# 2_waffling80-NMB_matrix.net
KiCad netlist of a schematic drawn in Altium Designer
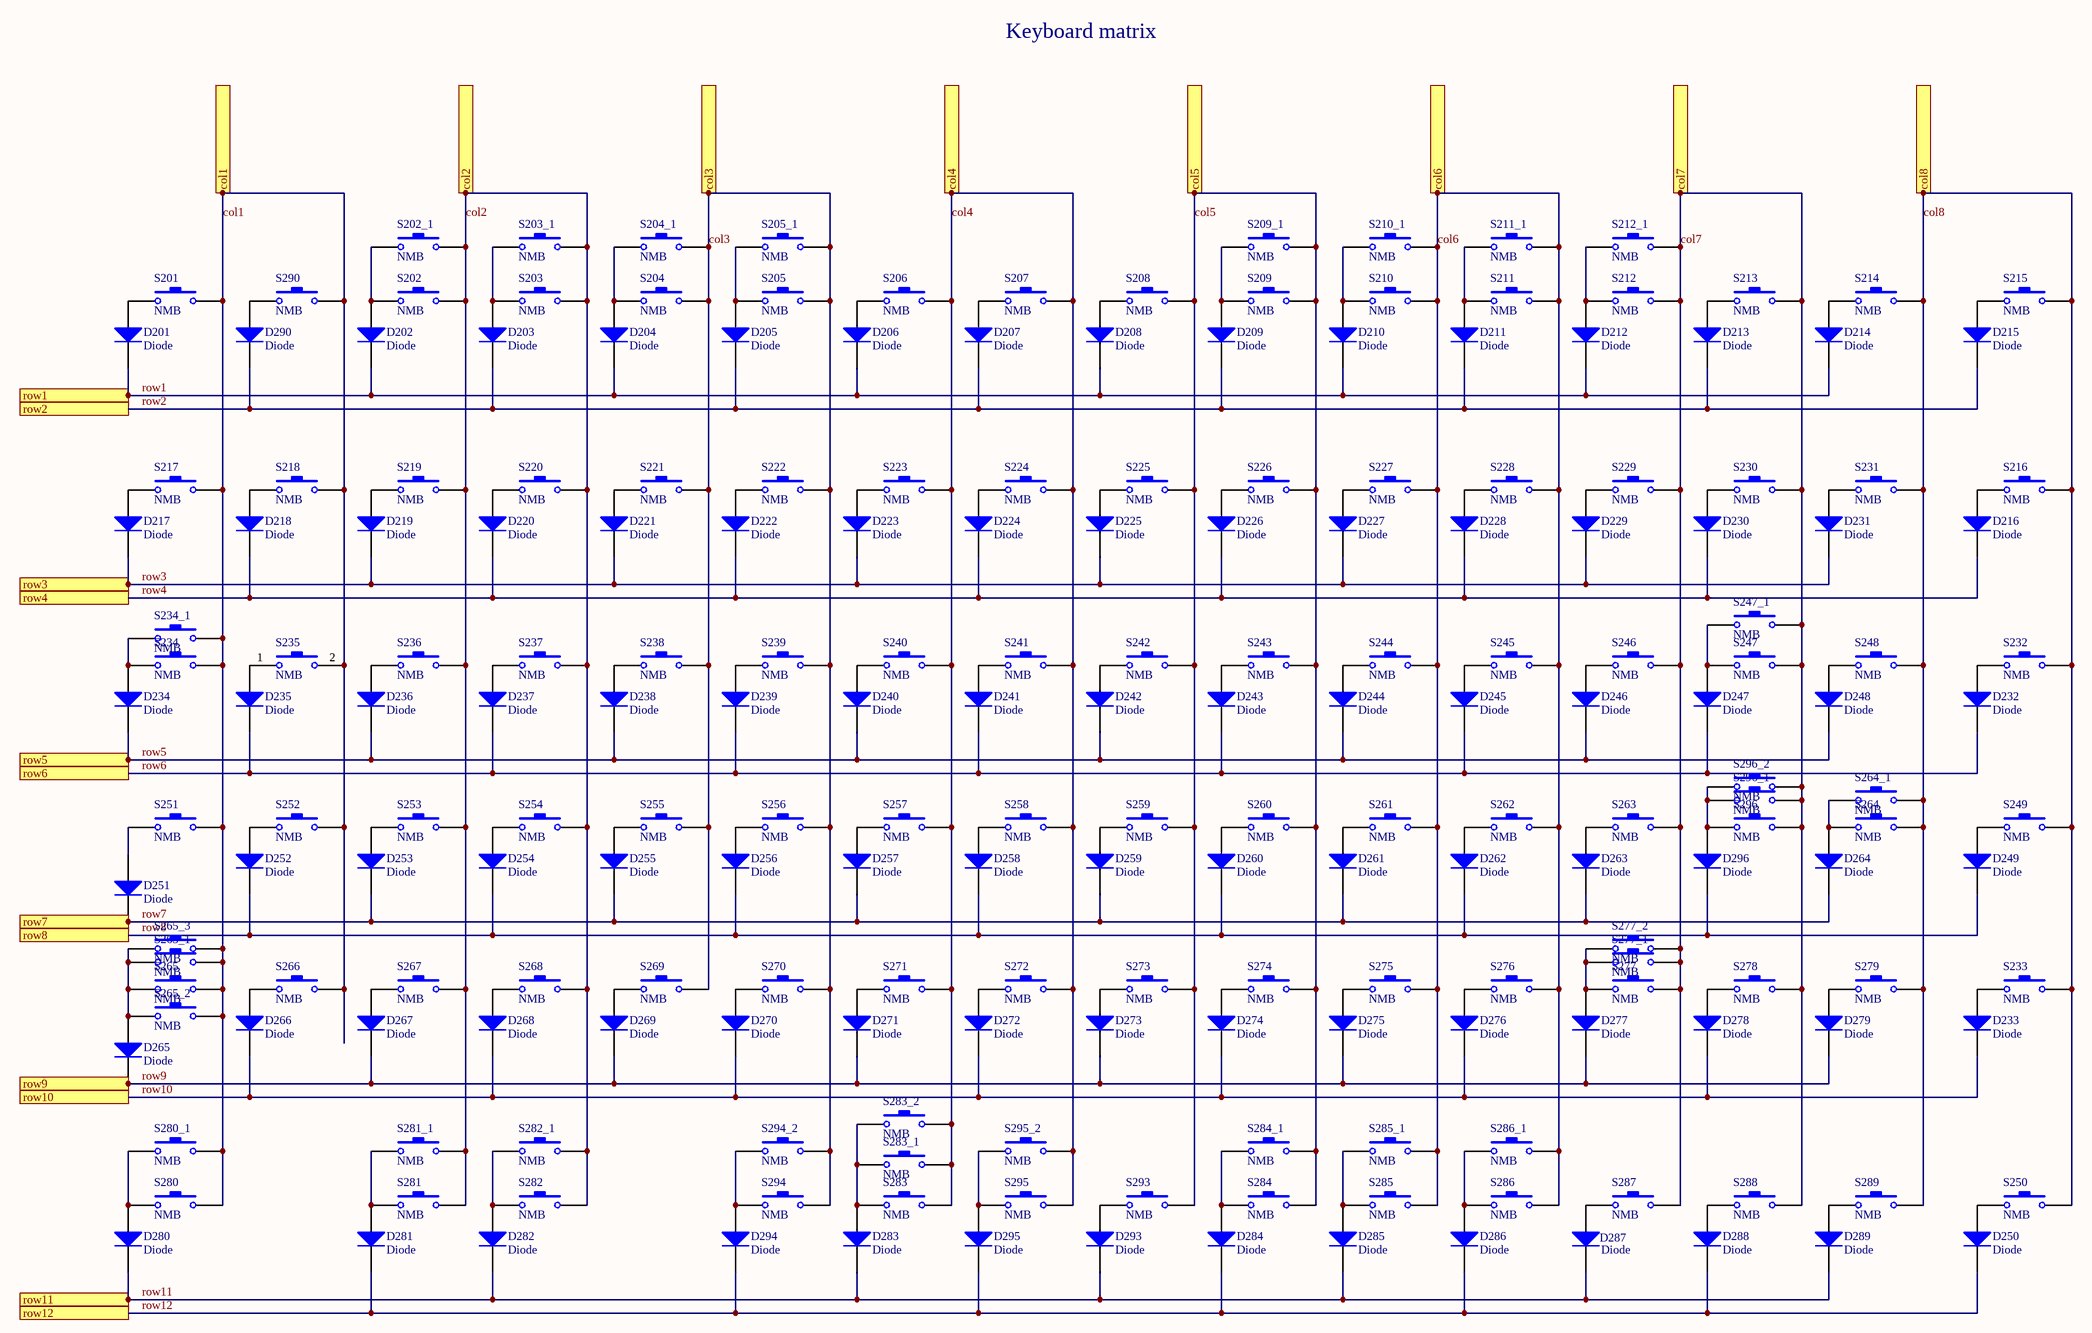
[diagram p0: 2_waffling80-NMB_matrix.SchDoc]

(export (version "E")
  (design (tool "Eeschema 10.0.6"))
  (components
    (comp (ref "D201")
      (value "Diode")
      (footprint "SOD-123")
      (description "Default Diode")
      (fields (field (name "LCSC PART #") "C81598") (field (name "MRF.PART") "1N4148W"))
      (libsource (lib "Miscellaneous Devices") (part "Diode"))
    )
    (comp (ref "D202")
      (value "Diode")
      (footprint "SOD-123")
      (description "Default Diode")
      (fields (field (name "LCSC PART #") "C81598") (field (name "MRF.PART") "1N4148W"))
      (libsource (lib "Miscellaneous Devices") (part "Diode"))
    )
    (comp (ref "D203")
      (value "Diode")
      (footprint "SOD-123")
      (description "Default Diode")
      (fields (field (name "LCSC PART #") "C81598") (field (name "MRF.PART") "1N4148W"))
      (libsource (lib "Miscellaneous Devices") (part "Diode"))
    )
    (comp (ref "D204")
      (value "Diode")
      (footprint "SOD-123")
      (description "Default Diode")
      (fields (field (name "LCSC PART #") "C81598") (field (name "MRF.PART") "1N4148W"))
      (libsource (lib "Miscellaneous Devices") (part "Diode"))
    )
    (comp (ref "D205")
      (value "Diode")
      (footprint "SOD-123")
      (description "Default Diode")
      (fields (field (name "LCSC PART #") "C81598") (field (name "MRF.PART") "1N4148W"))
      (libsource (lib "Miscellaneous Devices") (part "Diode"))
    )
    (comp (ref "D206")
      (value "Diode")
      (footprint "SOD-123")
      (description "Default Diode")
      (fields (field (name "LCSC PART #") "C81598") (field (name "MRF.PART") "1N4148W"))
      (libsource (lib "Miscellaneous Devices") (part "Diode"))
    )
    (comp (ref "D207")
      (value "Diode")
      (footprint "SOD-123")
      (description "Default Diode")
      (fields (field (name "LCSC PART #") "C81598") (field (name "MRF.PART") "1N4148W"))
      (libsource (lib "Miscellaneous Devices") (part "Diode"))
    )
    (comp (ref "D208")
      (value "Diode")
      (footprint "SOD-123")
      (description "Default Diode")
      (fields (field (name "LCSC PART #") "C81598") (field (name "MRF.PART") "1N4148W"))
      (libsource (lib "Miscellaneous Devices") (part "Diode"))
    )
    (comp (ref "D209")
      (value "Diode")
      (footprint "SOD-123")
      (description "Default Diode")
      (fields (field (name "LCSC PART #") "C81598") (field (name "MRF.PART") "1N4148W"))
      (libsource (lib "Miscellaneous Devices") (part "Diode"))
    )
    (comp (ref "D210")
      (value "Diode")
      (footprint "SOD-123")
      (description "Default Diode")
      (fields (field (name "LCSC PART #") "C81598") (field (name "MRF.PART") "1N4148W"))
      (libsource (lib "Miscellaneous Devices") (part "Diode"))
    )
    (comp (ref "D211")
      (value "Diode")
      (footprint "SOD-123")
      (description "Default Diode")
      (fields (field (name "LCSC PART #") "C81598") (field (name "MRF.PART") "1N4148W"))
      (libsource (lib "Miscellaneous Devices") (part "Diode"))
    )
    (comp (ref "D212")
      (value "Diode")
      (footprint "SOD-123")
      (description "Default Diode")
      (fields (field (name "LCSC PART #") "C81598") (field (name "MRF.PART") "1N4148W"))
      (libsource (lib "Miscellaneous Devices") (part "Diode"))
    )
    (comp (ref "D213")
      (value "Diode")
      (footprint "SOD-123")
      (description "Default Diode")
      (fields (field (name "LCSC PART #") "C81598") (field (name "MRF.PART") "1N4148W"))
      (libsource (lib "Miscellaneous Devices") (part "Diode"))
    )
    (comp (ref "D214")
      (value "Diode")
      (footprint "SOD-123")
      (description "Default Diode")
      (fields (field (name "LCSC PART #") "C81598") (field (name "MRF.PART") "1N4148W"))
      (libsource (lib "Miscellaneous Devices") (part "Diode"))
    )
    (comp (ref "D215")
      (value "Diode")
      (footprint "SOD-123")
      (description "Default Diode")
      (fields (field (name "LCSC PART #") "C81598") (field (name "MRF.PART") "1N4148W"))
      (libsource (lib "Miscellaneous Devices") (part "Diode"))
    )
    (comp (ref "D216")
      (value "Diode")
      (footprint "SOD-123")
      (description "Default Diode")
      (fields (field (name "LCSC PART #") "C81598") (field (name "MRF.PART") "1N4148W"))
      (libsource (lib "Miscellaneous Devices") (part "Diode"))
    )
    (comp (ref "D217")
      (value "Diode")
      (footprint "SOD-123")
      (description "Default Diode")
      (fields (field (name "LCSC PART #") "C81598") (field (name "MRF.PART") "1N4148W"))
      (libsource (lib "Miscellaneous Devices") (part "Diode"))
    )
    (comp (ref "D218")
      (value "Diode")
      (footprint "SOD-123")
      (description "Default Diode")
      (fields (field (name "LCSC PART #") "C81598") (field (name "MRF.PART") "1N4148W"))
      (libsource (lib "Miscellaneous Devices") (part "Diode"))
    )
    (comp (ref "D219")
      (value "Diode")
      (footprint "SOD-123")
      (description "Default Diode")
      (fields (field (name "LCSC PART #") "C81598") (field (name "MRF.PART") "1N4148W"))
      (libsource (lib "Miscellaneous Devices") (part "Diode"))
    )
    (comp (ref "D220")
      (value "Diode")
      (footprint "SOD-123")
      (description "Default Diode")
      (fields (field (name "LCSC PART #") "C81598") (field (name "MRF.PART") "1N4148W"))
      (libsource (lib "Miscellaneous Devices") (part "Diode"))
    )
    (comp (ref "D221")
      (value "Diode")
      (footprint "SOD-123")
      (description "Default Diode")
      (fields (field (name "LCSC PART #") "C81598") (field (name "MRF.PART") "1N4148W"))
      (libsource (lib "Miscellaneous Devices") (part "Diode"))
    )
    (comp (ref "D222")
      (value "Diode")
      (footprint "SOD-123")
      (description "Default Diode")
      (fields (field (name "LCSC PART #") "C81598") (field (name "MRF.PART") "1N4148W"))
      (libsource (lib "Miscellaneous Devices") (part "Diode"))
    )
    (comp (ref "D223")
      (value "Diode")
      (footprint "SOD-123")
      (description "Default Diode")
      (fields (field (name "LCSC PART #") "C81598") (field (name "MRF.PART") "1N4148W"))
      (libsource (lib "Miscellaneous Devices") (part "Diode"))
    )
    (comp (ref "D224")
      (value "Diode")
      (footprint "SOD-123")
      (description "Default Diode")
      (fields (field (name "LCSC PART #") "C81598") (field (name "MRF.PART") "1N4148W"))
      (libsource (lib "Miscellaneous Devices") (part "Diode"))
    )
    (comp (ref "D225")
      (value "Diode")
      (footprint "SOD-123")
      (description "Default Diode")
      (fields (field (name "LCSC PART #") "C81598") (field (name "MRF.PART") "1N4148W"))
      (libsource (lib "Miscellaneous Devices") (part "Diode"))
    )
    (comp (ref "D226")
      (value "Diode")
      (footprint "SOD-123")
      (description "Default Diode")
      (fields (field (name "LCSC PART #") "C81598") (field (name "MRF.PART") "1N4148W"))
      (libsource (lib "Miscellaneous Devices") (part "Diode"))
    )
    (comp (ref "D227")
      (value "Diode")
      (footprint "SOD-123")
      (description "Default Diode")
      (fields (field (name "LCSC PART #") "C81598") (field (name "MRF.PART") "1N4148W"))
      (libsource (lib "Miscellaneous Devices") (part "Diode"))
    )
    (comp (ref "D228")
      (value "Diode")
      (footprint "SOD-123")
      (description "Default Diode")
      (fields (field (name "LCSC PART #") "C81598") (field (name "MRF.PART") "1N4148W"))
      (libsource (lib "Miscellaneous Devices") (part "Diode"))
    )
    (comp (ref "D229")
      (value "Diode")
      (footprint "SOD-123")
      (description "Default Diode")
      (fields (field (name "LCSC PART #") "C81598") (field (name "MRF.PART") "1N4148W"))
      (libsource (lib "Miscellaneous Devices") (part "Diode"))
    )
    (comp (ref "D230")
      (value "Diode")
      (footprint "SOD-123")
      (description "Default Diode")
      (fields (field (name "LCSC PART #") "C81598") (field (name "MRF.PART") "1N4148W"))
      (libsource (lib "Miscellaneous Devices") (part "Diode"))
    )
    (comp (ref "D231")
      (value "Diode")
      (footprint "SOD-123")
      (description "Default Diode")
      (fields (field (name "LCSC PART #") "C81598") (field (name "MRF.PART") "1N4148W"))
      (libsource (lib "Miscellaneous Devices") (part "Diode"))
    )
    (comp (ref "D232")
      (value "Diode")
      (footprint "SOD-123")
      (description "Default Diode")
      (fields (field (name "LCSC PART #") "C81598") (field (name "MRF.PART") "1N4148W"))
      (libsource (lib "Miscellaneous Devices") (part "Diode"))
    )
    (comp (ref "D233")
      (value "Diode")
      (footprint "SOD-123")
      (description "Default Diode")
      (fields (field (name "LCSC PART #") "C81598") (field (name "MRF.PART") "1N4148W"))
      (libsource (lib "Miscellaneous Devices") (part "Diode"))
    )
    (comp (ref "D234")
      (value "Diode")
      (footprint "SOD-123")
      (description "Default Diode")
      (fields (field (name "LCSC PART #") "C81598") (field (name "MRF.PART") "1N4148W"))
      (libsource (lib "Miscellaneous Devices") (part "Diode"))
    )
    (comp (ref "D235")
      (value "Diode")
      (footprint "SOD-123")
      (description "Default Diode")
      (fields (field (name "LCSC PART #") "C81598") (field (name "MRF.PART") "1N4148W"))
      (libsource (lib "Miscellaneous Devices") (part "Diode"))
    )
    (comp (ref "D236")
      (value "Diode")
      (footprint "SOD-123")
      (description "Default Diode")
      (fields (field (name "LCSC PART #") "C81598") (field (name "MRF.PART") "1N4148W"))
      (libsource (lib "Miscellaneous Devices") (part "Diode"))
    )
    (comp (ref "D237")
      (value "Diode")
      (footprint "SOD-123")
      (description "Default Diode")
      (fields (field (name "LCSC PART #") "C81598") (field (name "MRF.PART") "1N4148W"))
      (libsource (lib "Miscellaneous Devices") (part "Diode"))
    )
    (comp (ref "D238")
      (value "Diode")
      (footprint "SOD-123")
      (description "Default Diode")
      (fields (field (name "LCSC PART #") "C81598") (field (name "MRF.PART") "1N4148W"))
      (libsource (lib "Miscellaneous Devices") (part "Diode"))
    )
    (comp (ref "D239")
      (value "Diode")
      (footprint "SOD-123")
      (description "Default Diode")
      (fields (field (name "LCSC PART #") "C81598") (field (name "MRF.PART") "1N4148W"))
      (libsource (lib "Miscellaneous Devices") (part "Diode"))
    )
    (comp (ref "D240")
      (value "Diode")
      (footprint "SOD-123")
      (description "Default Diode")
      (fields (field (name "LCSC PART #") "C81598") (field (name "MRF.PART") "1N4148W"))
      (libsource (lib "Miscellaneous Devices") (part "Diode"))
    )
    (comp (ref "D241")
      (value "Diode")
      (footprint "SOD-123")
      (description "Default Diode")
      (fields (field (name "LCSC PART #") "C81598") (field (name "MRF.PART") "1N4148W"))
      (libsource (lib "Miscellaneous Devices") (part "Diode"))
    )
    (comp (ref "D242")
      (value "Diode")
      (footprint "SOD-123")
      (description "Default Diode")
      (fields (field (name "LCSC PART #") "C81598") (field (name "MRF.PART") "1N4148W"))
      (libsource (lib "Miscellaneous Devices") (part "Diode"))
    )
    (comp (ref "D243")
      (value "Diode")
      (footprint "SOD-123")
      (description "Default Diode")
      (fields (field (name "LCSC PART #") "C81598") (field (name "MRF.PART") "1N4148W"))
      (libsource (lib "Miscellaneous Devices") (part "Diode"))
    )
    (comp (ref "D244")
      (value "Diode")
      (footprint "SOD-123")
      (description "Default Diode")
      (fields (field (name "LCSC PART #") "C81598") (field (name "MRF.PART") "1N4148W"))
      (libsource (lib "Miscellaneous Devices") (part "Diode"))
    )
    (comp (ref "D245")
      (value "Diode")
      (footprint "SOD-123")
      (description "Default Diode")
      (fields (field (name "LCSC PART #") "C81598") (field (name "MRF.PART") "1N4148W"))
      (libsource (lib "Miscellaneous Devices") (part "Diode"))
    )
    (comp (ref "D246")
      (value "Diode")
      (footprint "SOD-123")
      (description "Default Diode")
      (fields (field (name "LCSC PART #") "C81598") (field (name "MRF.PART") "1N4148W"))
      (libsource (lib "Miscellaneous Devices") (part "Diode"))
    )
    (comp (ref "D247")
      (value "Diode")
      (footprint "SOD-123")
      (description "Default Diode")
      (fields (field (name "LCSC PART #") "C81598") (field (name "MRF.PART") "1N4148W"))
      (libsource (lib "Miscellaneous Devices") (part "Diode"))
    )
    (comp (ref "D248")
      (value "Diode")
      (footprint "SOD-123")
      (description "Default Diode")
      (fields (field (name "LCSC PART #") "C81598") (field (name "MRF.PART") "1N4148W"))
      (libsource (lib "Miscellaneous Devices") (part "Diode"))
    )
    (comp (ref "D249")
      (value "Diode")
      (footprint "SOD-123")
      (description "Default Diode")
      (fields (field (name "LCSC PART #") "C81598") (field (name "MRF.PART") "1N4148W"))
      (libsource (lib "Miscellaneous Devices") (part "Diode"))
    )
    (comp (ref "D250")
      (value "Diode")
      (footprint "SOD-123")
      (description "Default Diode")
      (fields (field (name "LCSC PART #") "C81598") (field (name "MRF.PART") "1N4148W"))
      (libsource (lib "Miscellaneous Devices") (part "Diode"))
    )
    (comp (ref "D251")
      (value "Diode")
      (footprint "SOD-123")
      (description "Default Diode")
      (fields (field (name "LCSC PART #") "C81598") (field (name "MRF.PART") "1N4148W"))
      (libsource (lib "Miscellaneous Devices") (part "Diode"))
    )
    (comp (ref "D252")
      (value "Diode")
      (footprint "SOD-123")
      (description "Default Diode")
      (fields (field (name "LCSC PART #") "C81598") (field (name "MRF.PART") "1N4148W"))
      (libsource (lib "Miscellaneous Devices") (part "Diode"))
    )
    (comp (ref "D253")
      (value "Diode")
      (footprint "SOD-123")
      (description "Default Diode")
      (fields (field (name "LCSC PART #") "C81598") (field (name "MRF.PART") "1N4148W"))
      (libsource (lib "Miscellaneous Devices") (part "Diode"))
    )
    (comp (ref "D254")
      (value "Diode")
      (footprint "SOD-123")
      (description "Default Diode")
      (fields (field (name "LCSC PART #") "C81598") (field (name "MRF.PART") "1N4148W"))
      (libsource (lib "Miscellaneous Devices") (part "Diode"))
    )
    (comp (ref "D255")
      (value "Diode")
      (footprint "SOD-123")
      (description "Default Diode")
      (fields (field (name "LCSC PART #") "C81598") (field (name "MRF.PART") "1N4148W"))
      (libsource (lib "Miscellaneous Devices") (part "Diode"))
    )
    (comp (ref "D256")
      (value "Diode")
      (footprint "SOD-123")
      (description "Default Diode")
      (fields (field (name "LCSC PART #") "C81598") (field (name "MRF.PART") "1N4148W"))
      (libsource (lib "Miscellaneous Devices") (part "Diode"))
    )
    (comp (ref "D257")
      (value "Diode")
      (footprint "SOD-123")
      (description "Default Diode")
      (fields (field (name "LCSC PART #") "C81598") (field (name "MRF.PART") "1N4148W"))
      (libsource (lib "Miscellaneous Devices") (part "Diode"))
    )
    (comp (ref "D258")
      (value "Diode")
      (footprint "SOD-123")
      (description "Default Diode")
      (fields (field (name "LCSC PART #") "C81598") (field (name "MRF.PART") "1N4148W"))
      (libsource (lib "Miscellaneous Devices") (part "Diode"))
    )
    (comp (ref "D259")
      (value "Diode")
      (footprint "SOD-123")
      (description "Default Diode")
      (fields (field (name "LCSC PART #") "C81598") (field (name "MRF.PART") "1N4148W"))
      (libsource (lib "Miscellaneous Devices") (part "Diode"))
    )
    (comp (ref "D260")
      (value "Diode")
      (footprint "SOD-123")
      (description "Default Diode")
      (fields (field (name "LCSC PART #") "C81598") (field (name "MRF.PART") "1N4148W"))
      (libsource (lib "Miscellaneous Devices") (part "Diode"))
    )
    (comp (ref "D261")
      (value "Diode")
      (footprint "SOD-123")
      (description "Default Diode")
      (fields (field (name "LCSC PART #") "C81598") (field (name "MRF.PART") "1N4148W"))
      (libsource (lib "Miscellaneous Devices") (part "Diode"))
    )
    (comp (ref "D262")
      (value "Diode")
      (footprint "SOD-123")
      (description "Default Diode")
      (fields (field (name "LCSC PART #") "C81598") (field (name "MRF.PART") "1N4148W"))
      (libsource (lib "Miscellaneous Devices") (part "Diode"))
    )
    (comp (ref "D263")
      (value "Diode")
      (footprint "SOD-123")
      (description "Default Diode")
      (fields (field (name "LCSC PART #") "C81598") (field (name "MRF.PART") "1N4148W"))
      (libsource (lib "Miscellaneous Devices") (part "Diode"))
    )
    (comp (ref "D264")
      (value "Diode")
      (footprint "SOD-123")
      (description "Default Diode")
      (fields (field (name "LCSC PART #") "C81598") (field (name "MRF.PART") "1N4148W"))
      (libsource (lib "Miscellaneous Devices") (part "Diode"))
    )
    (comp (ref "D265")
      (value "Diode")
      (footprint "SOD-123")
      (description "Default Diode")
      (fields (field (name "LCSC PART #") "C81598") (field (name "MRF.PART") "1N4148W"))
      (libsource (lib "Miscellaneous Devices") (part "Diode"))
    )
    (comp (ref "D266")
      (value "Diode")
      (footprint "SOD-123")
      (description "Default Diode")
      (fields (field (name "LCSC PART #") "C81598") (field (name "MRF.PART") "1N4148W"))
      (libsource (lib "Miscellaneous Devices") (part "Diode"))
    )
    (comp (ref "D267")
      (value "Diode")
      (footprint "SOD-123")
      (description "Default Diode")
      (fields (field (name "LCSC PART #") "C81598") (field (name "MRF.PART") "1N4148W"))
      (libsource (lib "Miscellaneous Devices") (part "Diode"))
    )
    (comp (ref "D268")
      (value "Diode")
      (footprint "SOD-123")
      (description "Default Diode")
      (fields (field (name "LCSC PART #") "C81598") (field (name "MRF.PART") "1N4148W"))
      (libsource (lib "Miscellaneous Devices") (part "Diode"))
    )
    (comp (ref "D269")
      (value "Diode")
      (footprint "SOD-123")
      (description "Default Diode")
      (fields (field (name "LCSC PART #") "C81598") (field (name "MRF.PART") "1N4148W"))
      (libsource (lib "Miscellaneous Devices") (part "Diode"))
    )
    (comp (ref "D270")
      (value "Diode")
      (footprint "SOD-123")
      (description "Default Diode")
      (fields (field (name "LCSC PART #") "C81598") (field (name "MRF.PART") "1N4148W"))
      (libsource (lib "Miscellaneous Devices") (part "Diode"))
    )
    (comp (ref "D271")
      (value "Diode")
      (footprint "SOD-123")
      (description "Default Diode")
      (fields (field (name "LCSC PART #") "C81598") (field (name "MRF.PART") "1N4148W"))
      (libsource (lib "Miscellaneous Devices") (part "Diode"))
    )
    (comp (ref "D272")
      (value "Diode")
      (footprint "SOD-123")
      (description "Default Diode")
      (fields (field (name "LCSC PART #") "C81598") (field (name "MRF.PART") "1N4148W"))
      (libsource (lib "Miscellaneous Devices") (part "Diode"))
    )
    (comp (ref "D273")
      (value "Diode")
      (footprint "SOD-123")
      (description "Default Diode")
      (fields (field (name "LCSC PART #") "C81598") (field (name "MRF.PART") "1N4148W"))
      (libsource (lib "Miscellaneous Devices") (part "Diode"))
    )
    (comp (ref "D274")
      (value "Diode")
      (footprint "SOD-123")
      (description "Default Diode")
      (fields (field (name "LCSC PART #") "C81598") (field (name "MRF.PART") "1N4148W"))
      (libsource (lib "Miscellaneous Devices") (part "Diode"))
    )
    (comp (ref "D275")
      (value "Diode")
      (footprint "SOD-123")
      (description "Default Diode")
      (fields (field (name "LCSC PART #") "C81598") (field (name "MRF.PART") "1N4148W"))
      (libsource (lib "Miscellaneous Devices") (part "Diode"))
    )
    (comp (ref "D276")
      (value "Diode")
      (footprint "SOD-123")
      (description "Default Diode")
      (fields (field (name "LCSC PART #") "C81598") (field (name "MRF.PART") "1N4148W"))
      (libsource (lib "Miscellaneous Devices") (part "Diode"))
    )
    (comp (ref "D277")
      (value "Diode")
      (footprint "SOD-123")
      (description "Default Diode")
      (fields (field (name "LCSC PART #") "C81598") (field (name "MRF.PART") "1N4148W"))
      (libsource (lib "Miscellaneous Devices") (part "Diode"))
    )
    (comp (ref "D278")
      (value "Diode")
      (footprint "SOD-123")
      (description "Default Diode")
      (fields (field (name "LCSC PART #") "C81598") (field (name "MRF.PART") "1N4148W"))
      (libsource (lib "Miscellaneous Devices") (part "Diode"))
    )
    (comp (ref "D279")
      (value "Diode")
      (footprint "SOD-123")
      (description "Default Diode")
      (fields (field (name "LCSC PART #") "C81598") (field (name "MRF.PART") "1N4148W"))
      (libsource (lib "Miscellaneous Devices") (part "Diode"))
    )
    (comp (ref "D280")
      (value "Diode")
      (footprint "SOD-123")
      (description "Default Diode")
      (fields (field (name "LCSC PART #") "C81598") (field (name "MRF.PART") "1N4148W"))
      (libsource (lib "Miscellaneous Devices") (part "Diode"))
    )
    (comp (ref "D281")
      (value "Diode")
      (footprint "SOD-123")
      (description "Default Diode")
      (fields (field (name "LCSC PART #") "C81598") (field (name "MRF.PART") "1N4148W"))
      (libsource (lib "Miscellaneous Devices") (part "Diode"))
    )
    (comp (ref "D282")
      (value "Diode")
      (footprint "SOD-123")
      (description "Default Diode")
      (fields (field (name "LCSC PART #") "C81598") (field (name "MRF.PART") "1N4148W"))
      (libsource (lib "Miscellaneous Devices") (part "Diode"))
    )
    (comp (ref "D283")
      (value "Diode")
      (footprint "SOD-123")
      (description "Default Diode")
      (fields (field (name "LCSC PART #") "C81598") (field (name "MRF.PART") "1N4148W"))
      (libsource (lib "Miscellaneous Devices") (part "Diode"))
    )
    (comp (ref "D284")
      (value "Diode")
      (footprint "SOD-123")
      (description "Default Diode")
      (fields (field (name "LCSC PART #") "C81598") (field (name "MRF.PART") "1N4148W"))
      (libsource (lib "Miscellaneous Devices") (part "Diode"))
    )
    (comp (ref "D285")
      (value "Diode")
      (footprint "SOD-123")
      (description "Default Diode")
      (fields (field (name "LCSC PART #") "C81598") (field (name "MRF.PART") "1N4148W"))
      (libsource (lib "Miscellaneous Devices") (part "Diode"))
    )
    (comp (ref "D286")
      (value "Diode")
      (footprint "SOD-123")
      (description "Default Diode")
      (fields (field (name "LCSC PART #") "C81598") (field (name "MRF.PART") "1N4148W"))
      (libsource (lib "Miscellaneous Devices") (part "Diode"))
    )
    (comp (ref "D287")
      (value "Diode")
      (footprint "SOD-123")
      (description "Default Diode")
      (fields (field (name "LCSC PART #") "C81598") (field (name "MRF.PART") "1N4148W"))
      (libsource (lib "Miscellaneous Devices") (part "Diode"))
    )
    (comp (ref "D288")
      (value "Diode")
      (footprint "SOD-123")
      (description "Default Diode")
      (fields (field (name "LCSC PART #") "C81598") (field (name "MRF.PART") "1N4148W"))
      (libsource (lib "Miscellaneous Devices") (part "Diode"))
    )
    (comp (ref "D289")
      (value "Diode")
      (footprint "SOD-123")
      (description "Default Diode")
      (fields (field (name "LCSC PART #") "C81598") (field (name "MRF.PART") "1N4148W"))
      (libsource (lib "Miscellaneous Devices") (part "Diode"))
    )
    (comp (ref "D290")
      (value "Diode")
      (footprint "SOD-123")
      (description "Default Diode")
      (fields (field (name "LCSC PART #") "C81598") (field (name "MRF.PART") "1N4148W"))
      (libsource (lib "Miscellaneous Devices") (part "Diode"))
    )
    (comp (ref "D293")
      (value "Diode")
      (footprint "SOD-123")
      (description "Default Diode")
      (fields (field (name "LCSC PART #") "C81598") (field (name "MRF.PART") "1N4148W"))
      (libsource (lib "Miscellaneous Devices") (part "Diode"))
    )
    (comp (ref "D294")
      (value "Diode")
      (footprint "SOD-123")
      (description "Default Diode")
      (fields (field (name "LCSC PART #") "C81598") (field (name "MRF.PART") "1N4148W"))
      (libsource (lib "Miscellaneous Devices") (part "Diode"))
    )
    (comp (ref "D295")
      (value "Diode")
      (footprint "SOD-123")
      (description "Default Diode")
      (fields (field (name "LCSC PART #") "C81598") (field (name "MRF.PART") "1N4148W"))
      (libsource (lib "Miscellaneous Devices") (part "Diode"))
    )
    (comp (ref "D296")
      (value "Diode")
      (footprint "SOD-123")
      (description "Default Diode")
      (fields (field (name "LCSC PART #") "C81598") (field (name "MRF.PART") "1N4148W"))
      (libsource (lib "Miscellaneous Devices") (part "Diode"))
    )
    (comp (ref "S201")
      (value "NMB")
      (footprint "NMB-Switch 1U - switched pol  - no allignment pins")
      (description "Switch")
      (libsource (lib "Miscellaneous Devices") (part "SW-PB"))
    )
    (comp (ref "S202")
      (value "NMB")
      (footprint "NMB-Switch 1U - switched pol  - no allignment pins")
      (description "Switch")
      (libsource (lib "Miscellaneous Devices") (part "SW-PB"))
    )
    (comp (ref "S202_1")
      (value "NMB")
      (footprint "NMB-Switch 1U - no allignment pins")
      (description "Switch")
      (libsource (lib "Miscellaneous Devices") (part "SW-PB"))
    )
    (comp (ref "S203")
      (value "NMB")
      (footprint "NMB-Switch 1U - switched pol  - no allignment pins")
      (description "Switch")
      (libsource (lib "Miscellaneous Devices") (part "SW-PB"))
    )
    (comp (ref "S203_1")
      (value "NMB")
      (footprint "NMB-Switch 1U - no allignment pins")
      (description "Switch")
      (libsource (lib "Miscellaneous Devices") (part "SW-PB"))
    )
    (comp (ref "S204")
      (value "NMB")
      (footprint "NMB-Switch 1U - switched pol  - no allignment pins")
      (description "Switch")
      (libsource (lib "Miscellaneous Devices") (part "SW-PB"))
    )
    (comp (ref "S204_1")
      (value "NMB")
      (footprint "NMB-Switch 1U - no allignment pins")
      (description "Switch")
      (libsource (lib "Miscellaneous Devices") (part "SW-PB"))
    )
    (comp (ref "S205")
      (value "NMB")
      (footprint "NMB-Switch 1U - switched pol  - no allignment pins")
      (description "Switch")
      (libsource (lib "Miscellaneous Devices") (part "SW-PB"))
    )
    (comp (ref "S205_1")
      (value "NMB")
      (footprint "NMB-Switch 1U - no allignment pins")
      (description "Switch")
      (libsource (lib "Miscellaneous Devices") (part "SW-PB"))
    )
    (comp (ref "S206")
      (value "NMB")
      (footprint "NMB-Switch 1U - no allignment pins")
      (description "Switch")
      (libsource (lib "Miscellaneous Devices") (part "SW-PB"))
    )
    (comp (ref "S207")
      (value "NMB")
      (footprint "NMB-Switch 1U - no allignment pins")
      (description "Switch")
      (libsource (lib "Miscellaneous Devices") (part "SW-PB"))
    )
    (comp (ref "S208")
      (value "NMB")
      (footprint "NMB-Switch 1U - no allignment pins")
      (description "Switch")
      (libsource (lib "Miscellaneous Devices") (part "SW-PB"))
    )
    (comp (ref "S209")
      (value "NMB")
      (footprint "NMB-Switch 1U - switched pol  - no allignment pins")
      (description "Switch")
      (libsource (lib "Miscellaneous Devices") (part "SW-PB"))
    )
    (comp (ref "S209_1")
      (value "NMB")
      (footprint "NMB-Switch 1U - no allignment pins")
      (description "Switch")
      (libsource (lib "Miscellaneous Devices") (part "SW-PB"))
    )
    (comp (ref "S210")
      (value "NMB")
      (footprint "NMB-Switch 1U - no allignment pins")
      (description "Switch")
      (libsource (lib "Miscellaneous Devices") (part "SW-PB"))
    )
    (comp (ref "S210_1")
      (value "NMB")
      (footprint "NMB-Switch 1U - switched pol  - no allignment pins")
      (description "Switch")
      (libsource (lib "Miscellaneous Devices") (part "SW-PB"))
    )
    (comp (ref "S211")
      (value "NMB")
      (footprint "NMB-Switch 1U - no allignment pins")
      (description "Switch")
      (libsource (lib "Miscellaneous Devices") (part "SW-PB"))
    )
    (comp (ref "S211_1")
      (value "NMB")
      (footprint "NMB-Switch 1U - switched pol  - no allignment pins")
      (description "Switch")
      (libsource (lib "Miscellaneous Devices") (part "SW-PB"))
    )
    (comp (ref "S212")
      (value "NMB")
      (footprint "NMB-Switch 1U - no allignment pins")
      (description "Switch")
      (libsource (lib "Miscellaneous Devices") (part "SW-PB"))
    )
    (comp (ref "S212_1")
      (value "NMB")
      (footprint "NMB-Switch 1U - switched pol  - no allignment pins")
      (description "Switch")
      (libsource (lib "Miscellaneous Devices") (part "SW-PB"))
    )
    (comp (ref "S213")
      (value "NMB")
      (footprint "NMB-Switch 1U - no allignment pins")
      (description "Switch")
      (libsource (lib "Miscellaneous Devices") (part "SW-PB"))
    )
    (comp (ref "S214")
      (value "NMB")
      (footprint "NMB-Switch 1U - switched pol  - no allignment pins")
      (description "Switch")
      (libsource (lib "Miscellaneous Devices") (part "SW-PB"))
    )
    (comp (ref "S215")
      (value "NMB")
      (footprint "NMB-Switch 1U - no allignment pins")
      (description "Switch")
      (libsource (lib "Miscellaneous Devices") (part "SW-PB"))
    )
    (comp (ref "S216")
      (value "NMB")
      (footprint "NMB-Switch 1U - no allignment pins")
      (description "Switch")
      (libsource (lib "Miscellaneous Devices") (part "SW-PB"))
    )
    (comp (ref "S217")
      (value "NMB")
      (footprint "NMB-Switch 1U - switched pol  - no allignment pins")
      (description "Switch")
      (libsource (lib "Miscellaneous Devices") (part "SW-PB"))
    )
    (comp (ref "S218")
      (value "NMB")
      (footprint "NMB-Switch 1U - switched pol")
      (description "Switch")
      (libsource (lib "Miscellaneous Devices") (part "SW-PB"))
    )
    (comp (ref "S219")
      (value "NMB")
      (footprint "NMB-Switch 1U - switched pol  - no allignment pins")
      (description "Switch")
      (libsource (lib "Miscellaneous Devices") (part "SW-PB"))
    )
    (comp (ref "S220")
      (value "NMB")
      (footprint "NMB-Switch 1U - switched pol  - no allignment pins")
      (description "Switch")
      (libsource (lib "Miscellaneous Devices") (part "SW-PB"))
    )
    (comp (ref "S221")
      (value "NMB")
      (footprint "NMB-Switch 1U - switched pol  - no allignment pins")
      (description "Switch")
      (libsource (lib "Miscellaneous Devices") (part "SW-PB"))
    )
    (comp (ref "S222")
      (value "NMB")
      (footprint "NMB-Switch 1U - switched pol  - no allignment pins")
      (description "Switch")
      (libsource (lib "Miscellaneous Devices") (part "SW-PB"))
    )
    (comp (ref "S223")
      (value "NMB")
      (footprint "NMB-Switch 1U - switched pol  - no allignment pins")
      (description "Switch")
      (libsource (lib "Miscellaneous Devices") (part "SW-PB"))
    )
    (comp (ref "S224")
      (value "NMB")
      (footprint "NMB-Switch 1U - switched pol  - no allignment pins")
      (description "Switch")
      (libsource (lib "Miscellaneous Devices") (part "SW-PB"))
    )
    (comp (ref "S225")
      (value "NMB")
      (footprint "NMB-Switch 1U - switched pol  - no allignment pins")
      (description "Switch")
      (libsource (lib "Miscellaneous Devices") (part "SW-PB"))
    )
    (comp (ref "S226")
      (value "NMB")
      (footprint "NMB-Switch 1U - switched pol  - no allignment pins")
      (description "Switch")
      (libsource (lib "Miscellaneous Devices") (part "SW-PB"))
    )
    (comp (ref "S227")
      (value "NMB")
      (footprint "NMB-Switch 1U - switched pol  - no allignment pins")
      (description "Switch")
      (libsource (lib "Miscellaneous Devices") (part "SW-PB"))
    )
    (comp (ref "S228")
      (value "NMB")
      (footprint "NMB-Switch 1U - no allignment pins")
      (description "Switch")
      (libsource (lib "Miscellaneous Devices") (part "SW-PB"))
    )
    (comp (ref "S229")
      (value "NMB")
      (footprint "NMB-Switch 1U - switched pol  - no allignment pins")
      (description "Switch")
      (libsource (lib "Miscellaneous Devices") (part "SW-PB"))
    )
    (comp (ref "S230")
      (value "NMB")
      (footprint "NMB-Switch 1U - no allignment pins")
      (description "Switch")
      (libsource (lib "Miscellaneous Devices") (part "SW-PB"))
    )
    (comp (ref "S231")
      (value "NMB")
      (footprint "NMB-Switch 1U - no allignment pins")
      (description "Switch")
      (libsource (lib "Miscellaneous Devices") (part "SW-PB"))
    )
    (comp (ref "S232")
      (value "NMB")
      (footprint "NMB-Switch 1U")
      (description "Switch")
      (libsource (lib "Miscellaneous Devices") (part "SW-PB"))
    )
    (comp (ref "S233")
      (value "NMB")
      (footprint "NMB-Switch 1U - no allignment pins")
      (description "Switch")
      (libsource (lib "Miscellaneous Devices") (part "SW-PB"))
    )
    (comp (ref "S234")
      (value "NMB")
      (footprint "NMB-Switch 1U - switched pol  - no allignment pins")
      (description "TAB")
      (libsource (lib "Miscellaneous Devices") (part "SW-PB"))
    )
    (comp (ref "S234_1")
      (value "NMB")
      (footprint "NMB-Switch 1U - switched pol  - no allignment pins")
      (description "TAB")
      (libsource (lib "Miscellaneous Devices") (part "SW-PB"))
    )
    (comp (ref "S235")
      (value "NMB")
      (footprint "NMB-Switch 1U - switched pol  - no allignment pins")
      (description "Switch")
      (libsource (lib "") (part "SW-PB_1"))
    )
    (comp (ref "S236")
      (value "NMB")
      (footprint "NMB-Switch 1U - switched pol  - no allignment pins")
      (description "Switch")
      (libsource (lib "Miscellaneous Devices") (part "SW-PB"))
    )
    (comp (ref "S237")
      (value "NMB")
      (footprint "NMB-Switch 1U - switched pol  - no allignment pins")
      (description "Switch")
      (libsource (lib "Miscellaneous Devices") (part "SW-PB"))
    )
    (comp (ref "S238")
      (value "NMB")
      (footprint "NMB-Switch 1U - switched pol  - no allignment pins")
      (description "Switch")
      (libsource (lib "Miscellaneous Devices") (part "SW-PB"))
    )
    (comp (ref "S239")
      (value "NMB")
      (footprint "NMB-Switch 1U - switched pol  - no allignment pins")
      (description "Switch")
      (libsource (lib "Miscellaneous Devices") (part "SW-PB"))
    )
    (comp (ref "S240")
      (value "NMB")
      (footprint "NMB-Switch 1U - switched pol  - no allignment pins")
      (description "Switch")
      (libsource (lib "Miscellaneous Devices") (part "SW-PB"))
    )
    (comp (ref "S241")
      (value "NMB")
      (footprint "NMB-Switch 1U - switched pol  - no allignment pins")
      (description "Switch")
      (libsource (lib "Miscellaneous Devices") (part "SW-PB"))
    )
    (comp (ref "S242")
      (value "NMB")
      (footprint "NMB-Switch 1U - switched pol  - no allignment pins")
      (description "Switch")
      (libsource (lib "Miscellaneous Devices") (part "SW-PB"))
    )
    (comp (ref "S243")
      (value "NMB")
      (footprint "NMB-Switch 1U - switched pol  - no allignment pins")
      (description "Switch")
      (libsource (lib "Miscellaneous Devices") (part "SW-PB"))
    )
    (comp (ref "S244")
      (value "NMB")
      (footprint "NMB-Switch 1U - switched pol  - no allignment pins")
      (description "Switch")
      (libsource (lib "Miscellaneous Devices") (part "SW-PB"))
    )
    (comp (ref "S245")
      (value "NMB")
      (footprint "NMB-Switch 1U - switched pol  - no allignment pins")
      (description "Switch")
      (libsource (lib "Miscellaneous Devices") (part "SW-PB"))
    )
    (comp (ref "S246")
      (value "NMB")
      (footprint "NMB-Switch 1U - switched pol  - no allignment pins")
      (description "Switch")
      (libsource (lib "Miscellaneous Devices") (part "SW-PB"))
    )
    (comp (ref "S247")
      (value "NMB")
      (footprint "NMB-Switch 1U - no allignment pins")
      (description "Switch")
      (libsource (lib "Miscellaneous Devices") (part "SW-PB"))
    )
    (comp (ref "S247_1")
      (value "NMB")
      (footprint "NMB-Switch 1U - no allignment pins")
      (description "Switch")
      (libsource (lib "Miscellaneous Devices") (part "SW-PB"))
    )
    (comp (ref "S248")
      (value "NMB")
      (footprint "NMB-Switch 1U - no allignment pins")
      (description "Switch")
      (libsource (lib "Miscellaneous Devices") (part "SW-PB"))
    )
    (comp (ref "S249")
      (value "NMB")
      (footprint "NMB-Switch 1U - no allignment pins")
      (description "Switch")
      (libsource (lib "Miscellaneous Devices") (part "SW-PB"))
    )
    (comp (ref "S250")
      (value "NMB")
      (footprint "NMB-Switch 1U - no allignment pins")
      (description "Switch")
      (libsource (lib "Miscellaneous Devices") (part "SW-PB"))
    )
    (comp (ref "S251")
      (value "NMB")
      (footprint "NMB-Switch 1U - switched pol  - no allignment pins")
      (description "Switch")
      (libsource (lib "Miscellaneous Devices") (part "SW-PB"))
    )
    (comp (ref "S252")
      (value "NMB")
      (footprint "NMB-Switch 1U - switched pol  - no allignment pins")
      (description "Switch")
      (libsource (lib "Miscellaneous Devices") (part "SW-PB"))
    )
    (comp (ref "S253")
      (value "NMB")
      (footprint "NMB-Switch 1U - switched pol  - no allignment pins")
      (description "Switch")
      (libsource (lib "Miscellaneous Devices") (part "SW-PB"))
    )
    (comp (ref "S254")
      (value "NMB")
      (footprint "NMB-Switch 1U - switched pol  - no allignment pins")
      (description "Switch")
      (libsource (lib "Miscellaneous Devices") (part "SW-PB"))
    )
    (comp (ref "S255")
      (value "NMB")
      (footprint "NMB-Switch 1U - switched pol  - no allignment pins")
      (description "Switch")
      (libsource (lib "Miscellaneous Devices") (part "SW-PB"))
    )
    (comp (ref "S256")
      (value "NMB")
      (footprint "NMB-Switch 1U - switched pol  - no allignment pins")
      (description "Switch")
      (libsource (lib "Miscellaneous Devices") (part "SW-PB"))
    )
    (comp (ref "S257")
      (value "NMB")
      (footprint "NMB-Switch 1U - switched pol  - no allignment pins")
      (description "Switch")
      (libsource (lib "Miscellaneous Devices") (part "SW-PB"))
    )
    (comp (ref "S258")
      (value "NMB")
      (footprint "NMB-Switch 1U - switched pol")
      (description "Switch")
      (libsource (lib "Miscellaneous Devices") (part "SW-PB"))
    )
    (comp (ref "S259")
      (value "NMB")
      (footprint "NMB-Switch 1U - switched pol  - no allignment pins")
      (description "Switch")
      (libsource (lib "Miscellaneous Devices") (part "SW-PB"))
    )
    (comp (ref "S260")
      (value "NMB")
      (footprint "NMB-Switch 1U - switched pol  - no allignment pins")
      (description "Switch")
      (libsource (lib "Miscellaneous Devices") (part "SW-PB"))
    )
    (comp (ref "S261")
      (value "NMB")
      (footprint "NMB-Switch 1U - switched pol  - no allignment pins")
      (description "Switch")
      (libsource (lib "Miscellaneous Devices") (part "SW-PB"))
    )
    (comp (ref "S262")
      (value "NMB")
      (footprint "NMB-Switch 1U - switched pol  - no allignment pins")
      (description "Switch")
      (libsource (lib "Miscellaneous Devices") (part "SW-PB"))
    )
    (comp (ref "S263")
      (value "NMB")
      (footprint "NMB-Switch 1U - no allignment pins")
      (description "Switch")
      (libsource (lib "Miscellaneous Devices") (part "SW-PB"))
    )
    (comp (ref "S264")
      (value "NMB")
      (footprint "NMB-Switch 1U - no allignment pins")
      (description "Switch")
      (libsource (lib "Miscellaneous Devices") (part "SW-PB"))
    )
    (comp (ref "S264_1")
      (value "NMB")
      (footprint "NMB-Switch 1U - switched pol  - no allignment pins")
      (description "Switch")
      (libsource (lib "Miscellaneous Devices") (part "SW-PB"))
    )
    (comp (ref "S265")
      (value "NMB")
      (footprint "NMB-Switch 1U - no allignment pins")
      (description "Switch")
      (libsource (lib "Miscellaneous Devices") (part "SW-PB"))
    )
    (comp (ref "S265_1")
      (value "NMB")
      (footprint "NMB-Switch 1U - switched pol  - no allignment pins")
      (description "Switch")
      (libsource (lib "Miscellaneous Devices") (part "SW-PB"))
    )
    (comp (ref "S265_2")
      (value "NMB")
      (footprint "NMB-Switch 1U - no allignment pins")
      (description "Switch")
      (libsource (lib "Miscellaneous Devices") (part "SW-PB"))
    )
    (comp (ref "S265_3")
      (value "NMB")
      (footprint "NMB-Switch 1U - switched pol  - no allignment pins")
      (description "Switch")
      (libsource (lib "Miscellaneous Devices") (part "SW-PB"))
    )
    (comp (ref "S266")
      (value "NMB")
      (footprint "NMB-Switch 1U - switched pol")
      (description "Switch")
      (libsource (lib "Miscellaneous Devices") (part "SW-PB"))
    )
    (comp (ref "S267")
      (value "NMB")
      (footprint "NMB-Switch 1U - switched pol  - no allignment pins")
      (description "Switch")
      (libsource (lib "Miscellaneous Devices") (part "SW-PB"))
    )
    (comp (ref "S268")
      (value "NMB")
      (footprint "NMB-Switch 1U - switched pol  - no allignment pins")
      (description "Switch")
      (libsource (lib "Miscellaneous Devices") (part "SW-PB"))
    )
    (comp (ref "S269")
      (value "NMB")
      (footprint "NMB-Switch 1U - switched pol  - no allignment pins")
      (description "Switch")
      (libsource (lib "Miscellaneous Devices") (part "SW-PB"))
    )
    (comp (ref "S270")
      (value "NMB")
      (footprint "NMB-Switch 1U - switched pol  - no allignment pins")
      (description "Switch")
      (libsource (lib "Miscellaneous Devices") (part "SW-PB"))
    )
    (comp (ref "S271")
      (value "NMB")
      (footprint "NMB-Switch 1U - switched pol  - no allignment pins")
      (description "Switch")
      (libsource (lib "Miscellaneous Devices") (part "SW-PB"))
    )
    (comp (ref "S272")
      (value "NMB")
      (footprint "NMB-Switch 1U - switched pol  - no allignment pins")
      (description "Switch")
      (libsource (lib "Miscellaneous Devices") (part "SW-PB"))
    )
    (comp (ref "S273")
      (value "NMB")
      (footprint "NMB-Switch 1U - switched pol  - no allignment pins")
      (description "Switch")
      (libsource (lib "Miscellaneous Devices") (part "SW-PB"))
    )
    (comp (ref "S274")
      (value "NMB")
      (footprint "NMB-Switch 1U - switched pol  - no allignment pins")
      (description "Switch")
      (libsource (lib "Miscellaneous Devices") (part "SW-PB"))
    )
    (comp (ref "S275")
      (value "NMB")
      (footprint "NMB-Switch 1U - switched pol  - no allignment pins")
      (description "Switch")
      (libsource (lib "Miscellaneous Devices") (part "SW-PB"))
    )
    (comp (ref "S276")
      (value "NMB")
      (footprint "NMB-Switch 1U - switched pol  - no allignment pins")
      (description "Switch")
      (libsource (lib "Miscellaneous Devices") (part "SW-PB"))
    )
    (comp (ref "S277")
      (value "NMB")
      (footprint "NMB-Switch 1U - switched pol  - no allignment pins")
      (description "Switch")
      (libsource (lib "Miscellaneous Devices") (part "SW-PB"))
    )
    (comp (ref "S277_1")
      (value "NMB")
      (footprint "NMB-Switch 1U - no allignment pins")
      (description "Switch")
      (libsource (lib "Miscellaneous Devices") (part "SW-PB"))
    )
    (comp (ref "S277_2")
      (value "NMB")
      (footprint "NMB-Switch 1U - switched pol  - no allignment pins")
      (description "Switch")
      (libsource (lib "Miscellaneous Devices") (part "SW-PB"))
    )
    (comp (ref "S278")
      (value "NMB")
      (footprint "NMB-Switch 1U - switched pol  - no allignment pins")
      (description "Switch")
      (libsource (lib "Miscellaneous Devices") (part "SW-PB"))
    )
    (comp (ref "S279")
      (value "NMB")
      (footprint "NMB-Switch 1U")
      (description "Switch")
      (libsource (lib "Miscellaneous Devices") (part "SW-PB"))
    )
    (comp (ref "S280")
      (value "NMB")
      (footprint "NMB-Switch 1U - no allignment pins")
      (description "Switch")
      (libsource (lib "Miscellaneous Devices") (part "SW-PB"))
    )
    (comp (ref "S280_1")
      (value "NMB")
      (footprint "NMB-Switch 1U - switched pol  - no allignment pins")
      (description "Switch")
      (libsource (lib "Miscellaneous Devices") (part "SW-PB"))
    )
    (comp (ref "S281")
      (value "NMB")
      (footprint "NMB-Switch 1U - no allignment pins")
      (description "Switch")
      (libsource (lib "Miscellaneous Devices") (part "SW-PB"))
    )
    (comp (ref "S281_1")
      (value "NMB")
      (footprint "NMB-Switch 1U - switched pol  - no allignment pins")
      (description "Switch")
      (libsource (lib "Miscellaneous Devices") (part "SW-PB"))
    )
    (comp (ref "S282")
      (value "NMB")
      (footprint "NMB-Switch 1U - no allignment pins")
      (description "Switch")
      (libsource (lib "Miscellaneous Devices") (part "SW-PB"))
    )
    (comp (ref "S282_1")
      (value "NMB")
      (footprint "NMB-Switch 1U - switched pol  - no allignment pins")
      (description "Switch")
      (libsource (lib "Miscellaneous Devices") (part "SW-PB"))
    )
    (comp (ref "S283")
      (value "NMB")
      (footprint "NMB-Switch 1U - no allignment pins")
      (description "Switch")
      (libsource (lib "Miscellaneous Devices") (part "SW-PB"))
    )
    (comp (ref "S283_1")
      (value "NMB")
      (footprint "NMB-Switch 1U - switched pol  - no allignment pins")
      (description "Switch")
      (libsource (lib "Miscellaneous Devices") (part "SW-PB"))
    )
    (comp (ref "S283_2")
      (value "NMB")
      (footprint "NMB-Switch 1U - no allignment pins")
      (description "Switch")
      (libsource (lib "Miscellaneous Devices") (part "SW-PB"))
    )
    (comp (ref "S284")
      (value "NMB")
      (footprint "NMB-Switch 1U - no allignment pins")
      (description "Switch")
      (libsource (lib "Miscellaneous Devices") (part "SW-PB"))
    )
    (comp (ref "S284_1")
      (value "NMB")
      (footprint "NMB-Switch 1U - no allignment pins")
      (description "Switch")
      (libsource (lib "Miscellaneous Devices") (part "SW-PB"))
    )
    (comp (ref "S285")
      (value "NMB")
      (footprint "NMB-Switch 1U - no allignment pins")
      (description "Switch")
      (libsource (lib "Miscellaneous Devices") (part "SW-PB"))
    )
    (comp (ref "S285_1")
      (value "NMB")
      (footprint "NMB-Switch 1U - no allignment pins")
      (description "Switch")
      (libsource (lib "Miscellaneous Devices") (part "SW-PB"))
    )
    (comp (ref "S286")
      (value "NMB")
      (footprint "NMB-Switch 1U - no allignment pins")
      (description "Switch")
      (libsource (lib "Miscellaneous Devices") (part "SW-PB"))
    )
    (comp (ref "S286_1")
      (value "NMB")
      (footprint "NMB-Switch 1U - no allignment pins")
      (description "Switch")
      (libsource (lib "Miscellaneous Devices") (part "SW-PB"))
    )
    (comp (ref "S287")
      (value "NMB")
      (footprint "NMB-Switch 1U - no allignment pins")
      (description "Switch")
      (libsource (lib "Miscellaneous Devices") (part "SW-PB"))
    )
    (comp (ref "S288")
      (value "NMB")
      (footprint "NMB-Switch 1U - no allignment pins")
      (description "Switch")
      (libsource (lib "Miscellaneous Devices") (part "SW-PB"))
    )
    (comp (ref "S289")
      (value "NMB")
      (footprint "NMB-Switch 1U - no allignment pins")
      (description "Switch")
      (libsource (lib "Miscellaneous Devices") (part "SW-PB"))
    )
    (comp (ref "S290")
      (value "NMB")
      (footprint "NMB-Switch 1U - no allignment pins")
      (description "Switch")
      (libsource (lib "Miscellaneous Devices") (part "SW-PB"))
    )
    (comp (ref "S293")
      (value "NMB")
      (footprint "NMB-Switch 1U - no allignment pins")
      (description "Switch")
      (libsource (lib "Miscellaneous Devices") (part "SW-PB"))
    )
    (comp (ref "S294")
      (value "NMB")
      (footprint "NMB-Switch 1U - no allignment pins")
      (description "Switch")
      (libsource (lib "Miscellaneous Devices") (part "SW-PB"))
    )
    (comp (ref "S294_2")
      (value "NMB")
      (footprint "NMB-Switch 1U - no allignment pins")
      (description "Switch")
      (libsource (lib "Miscellaneous Devices") (part "SW-PB"))
    )
    (comp (ref "S295")
      (value "NMB")
      (footprint "NMB-Switch 1U - no allignment pins")
      (description "Switch")
      (libsource (lib "Miscellaneous Devices") (part "SW-PB"))
    )
    (comp (ref "S295_2")
      (value "NMB")
      (footprint "NMB-Switch 1U - no allignment pins")
      (description "Switch")
      (libsource (lib "Miscellaneous Devices") (part "SW-PB"))
    )
    (comp (ref "S296")
      (value "NMB")
      (footprint "NMB-Switch 1U - switched pol  - no allignment pins")
      (description "Switch")
      (libsource (lib "Miscellaneous Devices") (part "SW-PB"))
    )
    (comp (ref "S296_1")
      (value "NMB")
      (footprint "NMB-Switch 1U - no allignment pins")
      (description "Switch")
      (libsource (lib "Miscellaneous Devices") (part "SW-PB"))
    )
    (comp (ref "S296_2")
      (value "NMB")
      (footprint "NMB-Switch 1U - switched pol  - no allignment pins")
      (description "Switch")
      (libsource (lib "Miscellaneous Devices") (part "SW-PB"))
    )
  )
  (nets
    (net (code "1") (name "/col1") (class "Default")
      (node (ref "S201") (pin "2") (pinfunction "2_2") (pintype "passive"))
      (node (ref "S217") (pin "2") (pinfunction "2_2") (pintype "passive"))
      (node (ref "S218") (pin "2") (pinfunction "2_2") (pintype "passive"))
      (node (ref "S234") (pin "2") (pinfunction "2_2") (pintype "passive"))
      (node (ref "S234_1") (pin "2") (pinfunction "2_2") (pintype "passive"))
      (node (ref "S235") (pin "2") (pinfunction "2_2") (pintype "passive"))
      (node (ref "S251") (pin "2") (pinfunction "2_2") (pintype "passive"))
      (node (ref "S252") (pin "2") (pinfunction "2_2") (pintype "passive"))
      (node (ref "S265") (pin "2") (pinfunction "2_2") (pintype "passive"))
      (node (ref "S265_1") (pin "2") (pinfunction "2_2") (pintype "passive"))
      (node (ref "S265_2") (pin "2") (pinfunction "2_2") (pintype "passive"))
      (node (ref "S265_3") (pin "2") (pinfunction "2_2") (pintype "passive"))
      (node (ref "S266") (pin "2") (pinfunction "2_2") (pintype "passive"))
      (node (ref "S280") (pin "1") (pinfunction "1_1") (pintype "passive"))
      (node (ref "S280_1") (pin "2") (pinfunction "2_2") (pintype "passive"))
      (node (ref "S290") (pin "2") (pinfunction "2_2") (pintype "passive"))
    )
    (net (code "2") (name "/col2") (class "Default")
      (node (ref "S202") (pin "2") (pinfunction "2_2") (pintype "passive"))
      (node (ref "S202_1") (pin "2") (pinfunction "2_2") (pintype "passive"))
      (node (ref "S203") (pin "2") (pinfunction "2_2") (pintype "passive"))
      (node (ref "S203_1") (pin "2") (pinfunction "2_2") (pintype "passive"))
      (node (ref "S219") (pin "2") (pinfunction "2_2") (pintype "passive"))
      (node (ref "S220") (pin "2") (pinfunction "2_2") (pintype "passive"))
      (node (ref "S236") (pin "2") (pinfunction "2_2") (pintype "passive"))
      (node (ref "S237") (pin "2") (pinfunction "2_2") (pintype "passive"))
      (node (ref "S253") (pin "2") (pinfunction "2_2") (pintype "passive"))
      (node (ref "S254") (pin "2") (pinfunction "2_2") (pintype "passive"))
      (node (ref "S267") (pin "2") (pinfunction "2_2") (pintype "passive"))
      (node (ref "S268") (pin "2") (pinfunction "2_2") (pintype "passive"))
      (node (ref "S281") (pin "1") (pinfunction "1_1") (pintype "passive"))
      (node (ref "S281_1") (pin "2") (pinfunction "2_2") (pintype "passive"))
      (node (ref "S282") (pin "1") (pinfunction "1_1") (pintype "passive"))
      (node (ref "S282_1") (pin "2") (pinfunction "2_2") (pintype "passive"))
    )
    (net (code "3") (name "/col3") (class "Default")
      (node (ref "S204") (pin "2") (pinfunction "2_2") (pintype "passive"))
      (node (ref "S204_1") (pin "2") (pinfunction "2_2") (pintype "passive"))
      (node (ref "S205") (pin "2") (pinfunction "2_2") (pintype "passive"))
      (node (ref "S205_1") (pin "2") (pinfunction "2_2") (pintype "passive"))
      (node (ref "S221") (pin "2") (pinfunction "2_2") (pintype "passive"))
      (node (ref "S222") (pin "2") (pinfunction "2_2") (pintype "passive"))
      (node (ref "S238") (pin "2") (pinfunction "2_2") (pintype "passive"))
      (node (ref "S239") (pin "2") (pinfunction "2_2") (pintype "passive"))
      (node (ref "S255") (pin "2") (pinfunction "2_2") (pintype "passive"))
      (node (ref "S256") (pin "2") (pinfunction "2_2") (pintype "passive"))
      (node (ref "S269") (pin "2") (pinfunction "2_2") (pintype "passive"))
      (node (ref "S270") (pin "2") (pinfunction "2_2") (pintype "passive"))
      (node (ref "S294") (pin "1") (pinfunction "1_1") (pintype "passive"))
      (node (ref "S294_2") (pin "2") (pinfunction "2_2") (pintype "passive"))
    )
    (net (code "4") (name "/col4") (class "Default")
      (node (ref "S206") (pin "2") (pinfunction "2_2") (pintype "passive"))
      (node (ref "S207") (pin "2") (pinfunction "2_2") (pintype "passive"))
      (node (ref "S223") (pin "2") (pinfunction "2_2") (pintype "passive"))
      (node (ref "S224") (pin "2") (pinfunction "2_2") (pintype "passive"))
      (node (ref "S240") (pin "2") (pinfunction "2_2") (pintype "passive"))
      (node (ref "S241") (pin "2") (pinfunction "2_2") (pintype "passive"))
      (node (ref "S257") (pin "2") (pinfunction "2_2") (pintype "passive"))
      (node (ref "S258") (pin "2") (pinfunction "2_2") (pintype "passive"))
      (node (ref "S271") (pin "2") (pinfunction "2_2") (pintype "passive"))
      (node (ref "S272") (pin "2") (pinfunction "2_2") (pintype "passive"))
      (node (ref "S283") (pin "2") (pinfunction "2_2") (pintype "passive"))
      (node (ref "S283_1") (pin "2") (pinfunction "2_2") (pintype "passive"))
      (node (ref "S283_2") (pin "2") (pinfunction "2_2") (pintype "passive"))
      (node (ref "S295") (pin "1") (pinfunction "1_1") (pintype "passive"))
      (node (ref "S295_2") (pin "2") (pinfunction "2_2") (pintype "passive"))
    )
    (net (code "5") (name "/col5") (class "Default")
      (node (ref "S208") (pin "2") (pinfunction "2_2") (pintype "passive"))
      (node (ref "S209") (pin "2") (pinfunction "2_2") (pintype "passive"))
      (node (ref "S209_1") (pin "2") (pinfunction "2_2") (pintype "passive"))
      (node (ref "S225") (pin "2") (pinfunction "2_2") (pintype "passive"))
      (node (ref "S226") (pin "2") (pinfunction "2_2") (pintype "passive"))
      (node (ref "S242") (pin "2") (pinfunction "2_2") (pintype "passive"))
      (node (ref "S243") (pin "2") (pinfunction "2_2") (pintype "passive"))
      (node (ref "S259") (pin "2") (pinfunction "2_2") (pintype "passive"))
      (node (ref "S260") (pin "2") (pinfunction "2_2") (pintype "passive"))
      (node (ref "S273") (pin "2") (pinfunction "2_2") (pintype "passive"))
      (node (ref "S274") (pin "2") (pinfunction "2_2") (pintype "passive"))
      (node (ref "S284") (pin "2") (pinfunction "2_2") (pintype "passive"))
      (node (ref "S284_1") (pin "2") (pinfunction "2_2") (pintype "passive"))
      (node (ref "S293") (pin "2") (pinfunction "2_2") (pintype "passive"))
    )
    (net (code "6") (name "/col6") (class "Default")
      (node (ref "S210") (pin "2") (pinfunction "2_2") (pintype "passive"))
      (node (ref "S210_1") (pin "2") (pinfunction "2_2") (pintype "passive"))
      (node (ref "S211") (pin "2") (pinfunction "2_2") (pintype "passive"))
      (node (ref "S211_1") (pin "2") (pinfunction "2_2") (pintype "passive"))
      (node (ref "S227") (pin "2") (pinfunction "2_2") (pintype "passive"))
      (node (ref "S228") (pin "2") (pinfunction "2_2") (pintype "passive"))
      (node (ref "S244") (pin "2") (pinfunction "2_2") (pintype "passive"))
      (node (ref "S245") (pin "2") (pinfunction "2_2") (pintype "passive"))
      (node (ref "S261") (pin "2") (pinfunction "2_2") (pintype "passive"))
      (node (ref "S262") (pin "2") (pinfunction "2_2") (pintype "passive"))
      (node (ref "S275") (pin "2") (pinfunction "2_2") (pintype "passive"))
      (node (ref "S276") (pin "2") (pinfunction "2_2") (pintype "passive"))
      (node (ref "S285") (pin "2") (pinfunction "2_2") (pintype "passive"))
      (node (ref "S285_1") (pin "2") (pinfunction "2_2") (pintype "passive"))
      (node (ref "S286") (pin "2") (pinfunction "2_2") (pintype "passive"))
      (node (ref "S286_1") (pin "2") (pinfunction "2_2") (pintype "passive"))
    )
    (net (code "7") (name "/col7") (class "Default")
      (node (ref "S212") (pin "2") (pinfunction "2_2") (pintype "passive"))
      (node (ref "S212_1") (pin "2") (pinfunction "2_2") (pintype "passive"))
      (node (ref "S213") (pin "2") (pinfunction "2_2") (pintype "passive"))
      (node (ref "S229") (pin "2") (pinfunction "2_2") (pintype "passive"))
      (node (ref "S230") (pin "2") (pinfunction "2_2") (pintype "passive"))
      (node (ref "S246") (pin "2") (pinfunction "2_2") (pintype "passive"))
      (node (ref "S247") (pin "2") (pinfunction "2_2") (pintype "passive"))
      (node (ref "S247_1") (pin "2") (pinfunction "2_2") (pintype "passive"))
      (node (ref "S263") (pin "2") (pinfunction "2_2") (pintype "passive"))
      (node (ref "S277") (pin "2") (pinfunction "2_2") (pintype "passive"))
      (node (ref "S277_1") (pin "2") (pinfunction "2_2") (pintype "passive"))
      (node (ref "S277_2") (pin "2") (pinfunction "2_2") (pintype "passive"))
      (node (ref "S278") (pin "2") (pinfunction "2_2") (pintype "passive"))
      (node (ref "S287") (pin "2") (pinfunction "2_2") (pintype "passive"))
      (node (ref "S288") (pin "2") (pinfunction "2_2") (pintype "passive"))
      (node (ref "S296") (pin "2") (pinfunction "2_2") (pintype "passive"))
      (node (ref "S296_1") (pin "2") (pinfunction "2_2") (pintype "passive"))
      (node (ref "S296_2") (pin "2") (pinfunction "2_2") (pintype "passive"))
    )
    (net (code "8") (name "/col8") (class "Default")
      (node (ref "S214") (pin "2") (pinfunction "2_2") (pintype "passive"))
      (node (ref "S215") (pin "2") (pinfunction "2_2") (pintype "passive"))
      (node (ref "S216") (pin "2") (pinfunction "2_2") (pintype "passive"))
      (node (ref "S231") (pin "2") (pinfunction "2_2") (pintype "passive"))
      (node (ref "S232") (pin "2") (pinfunction "2_2") (pintype "passive"))
      (node (ref "S233") (pin "2") (pinfunction "2_2") (pintype "passive"))
      (node (ref "S248") (pin "2") (pinfunction "2_2") (pintype "passive"))
      (node (ref "S249") (pin "2") (pinfunction "2_2") (pintype "passive"))
      (node (ref "S250") (pin "2") (pinfunction "2_2") (pintype "passive"))
      (node (ref "S264") (pin "2") (pinfunction "2_2") (pintype "passive"))
      (node (ref "S264_1") (pin "2") (pinfunction "2_2") (pintype "passive"))
      (node (ref "S279") (pin "2") (pinfunction "2_2") (pintype "passive"))
      (node (ref "S289") (pin "2") (pinfunction "2_2") (pintype "passive"))
    )
    (net (code "9") (name "/row1") (class "Default")
      (node (ref "D201") (pin "2") (pinfunction "K_2") (pintype "passive"))
      (node (ref "D202") (pin "2") (pinfunction "K_2") (pintype "passive"))
      (node (ref "D204") (pin "2") (pinfunction "K_2") (pintype "passive"))
      (node (ref "D206") (pin "2") (pinfunction "K_2") (pintype "passive"))
      (node (ref "D208") (pin "2") (pinfunction "K_2") (pintype "passive"))
      (node (ref "D210") (pin "2") (pinfunction "K_2") (pintype "passive"))
      (node (ref "D212") (pin "2") (pinfunction "K_2") (pintype "passive"))
      (node (ref "D214") (pin "2") (pinfunction "K_2") (pintype "passive"))
    )
    (net (code "10") (name "/row2") (class "Default")
      (node (ref "D203") (pin "2") (pinfunction "K_2") (pintype "passive"))
      (node (ref "D205") (pin "2") (pinfunction "K_2") (pintype "passive"))
      (node (ref "D207") (pin "2") (pinfunction "K_2") (pintype "passive"))
      (node (ref "D209") (pin "2") (pinfunction "K_2") (pintype "passive"))
      (node (ref "D211") (pin "2") (pinfunction "K_2") (pintype "passive"))
      (node (ref "D213") (pin "2") (pinfunction "K_2") (pintype "passive"))
      (node (ref "D215") (pin "2") (pinfunction "K_2") (pintype "passive"))
      (node (ref "D290") (pin "2") (pinfunction "K_2") (pintype "passive"))
    )
    (net (code "11") (name "/row3") (class "Default")
      (node (ref "D217") (pin "2") (pinfunction "K_2") (pintype "passive"))
      (node (ref "D219") (pin "2") (pinfunction "K_2") (pintype "passive"))
      (node (ref "D221") (pin "2") (pinfunction "K_2") (pintype "passive"))
      (node (ref "D223") (pin "2") (pinfunction "K_2") (pintype "passive"))
      (node (ref "D225") (pin "2") (pinfunction "K_2") (pintype "passive"))
      (node (ref "D227") (pin "2") (pinfunction "K_2") (pintype "passive"))
      (node (ref "D229") (pin "2") (pinfunction "K_2") (pintype "passive"))
      (node (ref "D231") (pin "2") (pinfunction "K_2") (pintype "passive"))
    )
    (net (code "12") (name "/row4") (class "Default")
      (node (ref "D216") (pin "2") (pinfunction "K_2") (pintype "passive"))
      (node (ref "D218") (pin "2") (pinfunction "K_2") (pintype "passive"))
      (node (ref "D220") (pin "2") (pinfunction "K_2") (pintype "passive"))
      (node (ref "D222") (pin "2") (pinfunction "K_2") (pintype "passive"))
      (node (ref "D224") (pin "2") (pinfunction "K_2") (pintype "passive"))
      (node (ref "D226") (pin "2") (pinfunction "K_2") (pintype "passive"))
      (node (ref "D228") (pin "2") (pinfunction "K_2") (pintype "passive"))
      (node (ref "D230") (pin "2") (pinfunction "K_2") (pintype "passive"))
    )
    (net (code "13") (name "/row5") (class "Default")
      (node (ref "D234") (pin "2") (pinfunction "K_2") (pintype "passive"))
      (node (ref "D236") (pin "2") (pinfunction "K_2") (pintype "passive"))
      (node (ref "D238") (pin "2") (pinfunction "K_2") (pintype "passive"))
      (node (ref "D240") (pin "2") (pinfunction "K_2") (pintype "passive"))
      (node (ref "D242") (pin "2") (pinfunction "K_2") (pintype "passive"))
      (node (ref "D244") (pin "2") (pinfunction "K_2") (pintype "passive"))
      (node (ref "D246") (pin "2") (pinfunction "K_2") (pintype "passive"))
      (node (ref "D248") (pin "2") (pinfunction "K_2") (pintype "passive"))
    )
    (net (code "14") (name "/row6") (class "Default")
      (node (ref "D232") (pin "2") (pinfunction "K_2") (pintype "passive"))
      (node (ref "D235") (pin "2") (pinfunction "K_2") (pintype "passive"))
      (node (ref "D237") (pin "2") (pinfunction "K_2") (pintype "passive"))
      (node (ref "D239") (pin "2") (pinfunction "K_2") (pintype "passive"))
      (node (ref "D241") (pin "2") (pinfunction "K_2") (pintype "passive"))
      (node (ref "D243") (pin "2") (pinfunction "K_2") (pintype "passive"))
      (node (ref "D245") (pin "2") (pinfunction "K_2") (pintype "passive"))
      (node (ref "D247") (pin "2") (pinfunction "K_2") (pintype "passive"))
    )
    (net (code "15") (name "/row7") (class "Default")
      (node (ref "D251") (pin "2") (pinfunction "K_2") (pintype "passive"))
      (node (ref "D253") (pin "2") (pinfunction "K_2") (pintype "passive"))
      (node (ref "D255") (pin "2") (pinfunction "K_2") (pintype "passive"))
      (node (ref "D257") (pin "2") (pinfunction "K_2") (pintype "passive"))
      (node (ref "D259") (pin "2") (pinfunction "K_2") (pintype "passive"))
      (node (ref "D261") (pin "2") (pinfunction "K_2") (pintype "passive"))
      (node (ref "D263") (pin "2") (pinfunction "K_2") (pintype "passive"))
      (node (ref "D264") (pin "2") (pinfunction "K_2") (pintype "passive"))
    )
    (net (code "16") (name "/row8") (class "Default")
      (node (ref "D249") (pin "2") (pinfunction "K_2") (pintype "passive"))
      (node (ref "D252") (pin "2") (pinfunction "K_2") (pintype "passive"))
      (node (ref "D254") (pin "2") (pinfunction "K_2") (pintype "passive"))
      (node (ref "D256") (pin "2") (pinfunction "K_2") (pintype "passive"))
      (node (ref "D258") (pin "2") (pinfunction "K_2") (pintype "passive"))
      (node (ref "D260") (pin "2") (pinfunction "K_2") (pintype "passive"))
      (node (ref "D262") (pin "2") (pinfunction "K_2") (pintype "passive"))
      (node (ref "D296") (pin "2") (pinfunction "K_2") (pintype "passive"))
    )
    (net (code "17") (name "/row9") (class "Default")
      (node (ref "D265") (pin "2") (pinfunction "K_2") (pintype "passive"))
      (node (ref "D267") (pin "2") (pinfunction "K_2") (pintype "passive"))
      (node (ref "D269") (pin "2") (pinfunction "K_2") (pintype "passive"))
      (node (ref "D271") (pin "2") (pinfunction "K_2") (pintype "passive"))
      (node (ref "D273") (pin "2") (pinfunction "K_2") (pintype "passive"))
      (node (ref "D275") (pin "2") (pinfunction "K_2") (pintype "passive"))
      (node (ref "D277") (pin "2") (pinfunction "K_2") (pintype "passive"))
      (node (ref "D279") (pin "2") (pinfunction "K_2") (pintype "passive"))
    )
    (net (code "18") (name "/row10") (class "Default")
      (node (ref "D233") (pin "2") (pinfunction "K_2") (pintype "passive"))
      (node (ref "D266") (pin "2") (pinfunction "K_2") (pintype "passive"))
      (node (ref "D268") (pin "2") (pinfunction "K_2") (pintype "passive"))
      (node (ref "D270") (pin "2") (pinfunction "K_2") (pintype "passive"))
      (node (ref "D272") (pin "2") (pinfunction "K_2") (pintype "passive"))
      (node (ref "D274") (pin "2") (pinfunction "K_2") (pintype "passive"))
      (node (ref "D276") (pin "2") (pinfunction "K_2") (pintype "passive"))
      (node (ref "D278") (pin "2") (pinfunction "K_2") (pintype "passive"))
    )
    (net (code "19") (name "/row11") (class "Default")
      (node (ref "D280") (pin "2") (pinfunction "K_2") (pintype "passive"))
      (node (ref "D282") (pin "2") (pinfunction "K_2") (pintype "passive"))
      (node (ref "D283") (pin "2") (pinfunction "K_2") (pintype "passive"))
      (node (ref "D285") (pin "2") (pinfunction "K_2") (pintype "passive"))
      (node (ref "D287") (pin "2") (pinfunction "K_2") (pintype "passive"))
      (node (ref "D289") (pin "2") (pinfunction "K_2") (pintype "passive"))
      (node (ref "D293") (pin "2") (pinfunction "K_2") (pintype "passive"))
    )
    (net (code "20") (name "/row12") (class "Default")
      (node (ref "D250") (pin "2") (pinfunction "K_2") (pintype "passive"))
      (node (ref "D281") (pin "2") (pinfunction "K_2") (pintype "passive"))
      (node (ref "D284") (pin "2") (pinfunction "K_2") (pintype "passive"))
      (node (ref "D286") (pin "2") (pinfunction "K_2") (pintype "passive"))
      (node (ref "D288") (pin "2") (pinfunction "K_2") (pintype "passive"))
      (node (ref "D294") (pin "2") (pinfunction "K_2") (pintype "passive"))
      (node (ref "D295") (pin "2") (pinfunction "K_2") (pintype "passive"))
    )
    (net (code "21") (name "Net-(D201-A)") (class "Default")
      (node (ref "D201") (pin "1") (pinfunction "A_1") (pintype "passive"))
      (node (ref "S201") (pin "1") (pinfunction "1_1") (pintype "passive"))
    )
    (net (code "22") (name "Net-(D202-A)") (class "Default")
      (node (ref "D202") (pin "1") (pinfunction "A_1") (pintype "passive"))
      (node (ref "S202") (pin "1") (pinfunction "1_1") (pintype "passive"))
      (node (ref "S202_1") (pin "1") (pinfunction "1_1") (pintype "passive"))
    )
    (net (code "23") (name "Net-(D203-A)") (class "Default")
      (node (ref "D203") (pin "1") (pinfunction "A_1") (pintype "passive"))
      (node (ref "S203") (pin "1") (pinfunction "1_1") (pintype "passive"))
      (node (ref "S203_1") (pin "1") (pinfunction "1_1") (pintype "passive"))
    )
    (net (code "24") (name "Net-(D204-A)") (class "Default")
      (node (ref "D204") (pin "1") (pinfunction "A_1") (pintype "passive"))
      (node (ref "S204") (pin "1") (pinfunction "1_1") (pintype "passive"))
      (node (ref "S204_1") (pin "1") (pinfunction "1_1") (pintype "passive"))
    )
    (net (code "25") (name "Net-(D205-A)") (class "Default")
      (node (ref "D205") (pin "1") (pinfunction "A_1") (pintype "passive"))
      (node (ref "S205") (pin "1") (pinfunction "1_1") (pintype "passive"))
      (node (ref "S205_1") (pin "1") (pinfunction "1_1") (pintype "passive"))
    )
    (net (code "26") (name "Net-(D206-A)") (class "Default")
      (node (ref "D206") (pin "1") (pinfunction "A_1") (pintype "passive"))
      (node (ref "S206") (pin "1") (pinfunction "1_1") (pintype "passive"))
    )
    (net (code "27") (name "Net-(D207-A)") (class "Default")
      (node (ref "D207") (pin "1") (pinfunction "A_1") (pintype "passive"))
      (node (ref "S207") (pin "1") (pinfunction "1_1") (pintype "passive"))
    )
    (net (code "28") (name "Net-(D208-A)") (class "Default")
      (node (ref "D208") (pin "1") (pinfunction "A_1") (pintype "passive"))
      (node (ref "S208") (pin "1") (pinfunction "1_1") (pintype "passive"))
    )
    (net (code "29") (name "Net-(D209-A)") (class "Default")
      (node (ref "D209") (pin "1") (pinfunction "A_1") (pintype "passive"))
      (node (ref "S209") (pin "1") (pinfunction "1_1") (pintype "passive"))
      (node (ref "S209_1") (pin "1") (pinfunction "1_1") (pintype "passive"))
    )
    (net (code "30") (name "Net-(D210-A)") (class "Default")
      (node (ref "D210") (pin "1") (pinfunction "A_1") (pintype "passive"))
      (node (ref "S210") (pin "1") (pinfunction "1_1") (pintype "passive"))
      (node (ref "S210_1") (pin "1") (pinfunction "1_1") (pintype "passive"))
    )
    (net (code "31") (name "Net-(D211-A)") (class "Default")
      (node (ref "D211") (pin "1") (pinfunction "A_1") (pintype "passive"))
      (node (ref "S211") (pin "1") (pinfunction "1_1") (pintype "passive"))
      (node (ref "S211_1") (pin "1") (pinfunction "1_1") (pintype "passive"))
    )
    (net (code "32") (name "Net-(D212-A)") (class "Default")
      (node (ref "D212") (pin "1") (pinfunction "A_1") (pintype "passive"))
      (node (ref "S212") (pin "1") (pinfunction "1_1") (pintype "passive"))
      (node (ref "S212_1") (pin "1") (pinfunction "1_1") (pintype "passive"))
    )
    (net (code "33") (name "Net-(D213-A)") (class "Default")
      (node (ref "D213") (pin "1") (pinfunction "A_1") (pintype "passive"))
      (node (ref "S213") (pin "1") (pinfunction "1_1") (pintype "passive"))
    )
    (net (code "34") (name "Net-(D214-A)") (class "Default")
      (node (ref "D214") (pin "1") (pinfunction "A_1") (pintype "passive"))
      (node (ref "S214") (pin "1") (pinfunction "1_1") (pintype "passive"))
    )
    (net (code "35") (name "Net-(D215-A)") (class "Default")
      (node (ref "D215") (pin "1") (pinfunction "A_1") (pintype "passive"))
      (node (ref "S215") (pin "1") (pinfunction "1_1") (pintype "passive"))
    )
    (net (code "36") (name "Net-(D216-A)") (class "Default")
      (node (ref "D216") (pin "1") (pinfunction "A_1") (pintype "passive"))
      (node (ref "S216") (pin "1") (pinfunction "1_1") (pintype "passive"))
    )
    (net (code "37") (name "Net-(D217-A)") (class "Default")
      (node (ref "D217") (pin "1") (pinfunction "A_1") (pintype "passive"))
      (node (ref "S217") (pin "1") (pinfunction "1_1") (pintype "passive"))
    )
    (net (code "38") (name "Net-(D218-A)") (class "Default")
      (node (ref "D218") (pin "1") (pinfunction "A_1") (pintype "passive"))
      (node (ref "S218") (pin "1") (pinfunction "1_1") (pintype "passive"))
    )
    (net (code "39") (name "Net-(D219-A)") (class "Default")
      (node (ref "D219") (pin "1") (pinfunction "A_1") (pintype "passive"))
      (node (ref "S219") (pin "1") (pinfunction "1_1") (pintype "passive"))
    )
    (net (code "40") (name "Net-(D220-A)") (class "Default")
      (node (ref "D220") (pin "1") (pinfunction "A_1") (pintype "passive"))
      (node (ref "S220") (pin "1") (pinfunction "1_1") (pintype "passive"))
    )
    (net (code "41") (name "Net-(D221-A)") (class "Default")
      (node (ref "D221") (pin "1") (pinfunction "A_1") (pintype "passive"))
      (node (ref "S221") (pin "1") (pinfunction "1_1") (pintype "passive"))
    )
    (net (code "42") (name "Net-(D222-A)") (class "Default")
      (node (ref "D222") (pin "1") (pinfunction "A_1") (pintype "passive"))
      (node (ref "S222") (pin "1") (pinfunction "1_1") (pintype "passive"))
    )
    (net (code "43") (name "Net-(D223-A)") (class "Default")
      (node (ref "D223") (pin "1") (pinfunction "A_1") (pintype "passive"))
      (node (ref "S223") (pin "1") (pinfunction "1_1") (pintype "passive"))
    )
    (net (code "44") (name "Net-(D224-A)") (class "Default")
      (node (ref "D224") (pin "1") (pinfunction "A_1") (pintype "passive"))
      (node (ref "S224") (pin "1") (pinfunction "1_1") (pintype "passive"))
    )
    (net (code "45") (name "Net-(D225-A)") (class "Default")
      (node (ref "D225") (pin "1") (pinfunction "A_1") (pintype "passive"))
      (node (ref "S225") (pin "1") (pinfunction "1_1") (pintype "passive"))
    )
    (net (code "46") (name "Net-(D226-A)") (class "Default")
      (node (ref "D226") (pin "1") (pinfunction "A_1") (pintype "passive"))
      (node (ref "S226") (pin "1") (pinfunction "1_1") (pintype "passive"))
    )
    (net (code "47") (name "Net-(D227-A)") (class "Default")
      (node (ref "D227") (pin "1") (pinfunction "A_1") (pintype "passive"))
      (node (ref "S227") (pin "1") (pinfunction "1_1") (pintype "passive"))
    )
    (net (code "48") (name "Net-(D228-A)") (class "Default")
      (node (ref "D228") (pin "1") (pinfunction "A_1") (pintype "passive"))
      (node (ref "S228") (pin "1") (pinfunction "1_1") (pintype "passive"))
    )
    (net (code "49") (name "Net-(D229-A)") (class "Default")
      (node (ref "D229") (pin "1") (pinfunction "A_1") (pintype "passive"))
      (node (ref "S229") (pin "1") (pinfunction "1_1") (pintype "passive"))
    )
    (net (code "50") (name "Net-(D230-A)") (class "Default")
      (node (ref "D230") (pin "1") (pinfunction "A_1") (pintype "passive"))
      (node (ref "S230") (pin "1") (pinfunction "1_1") (pintype "passive"))
    )
    (net (code "51") (name "Net-(D231-A)") (class "Default")
      (node (ref "D231") (pin "1") (pinfunction "A_1") (pintype "passive"))
      (node (ref "S231") (pin "1") (pinfunction "1_1") (pintype "passive"))
    )
    (net (code "52") (name "Net-(D232-A)") (class "Default")
      (node (ref "D232") (pin "1") (pinfunction "A_1") (pintype "passive"))
      (node (ref "S232") (pin "1") (pinfunction "1_1") (pintype "passive"))
    )
    (net (code "53") (name "Net-(D233-A)") (class "Default")
      (node (ref "D233") (pin "1") (pinfunction "A_1") (pintype "passive"))
      (node (ref "S233") (pin "1") (pinfunction "1_1") (pintype "passive"))
    )
    (net (code "54") (name "Net-(D234-A)") (class "Default")
      (node (ref "D234") (pin "1") (pinfunction "A_1") (pintype "passive"))
      (node (ref "S234") (pin "1") (pinfunction "1_1") (pintype "passive"))
      (node (ref "S234_1") (pin "1") (pinfunction "1_1") (pintype "passive"))
    )
    (net (code "55") (name "Net-(D235-A)") (class "Default")
      (node (ref "D235") (pin "1") (pinfunction "A_1") (pintype "passive"))
      (node (ref "S235") (pin "1") (pinfunction "1_1") (pintype "passive"))
    )
    (net (code "56") (name "Net-(D236-A)") (class "Default")
      (node (ref "D236") (pin "1") (pinfunction "A_1") (pintype "passive"))
      (node (ref "S236") (pin "1") (pinfunction "1_1") (pintype "passive"))
    )
    (net (code "57") (name "Net-(D237-A)") (class "Default")
      (node (ref "D237") (pin "1") (pinfunction "A_1") (pintype "passive"))
      (node (ref "S237") (pin "1") (pinfunction "1_1") (pintype "passive"))
    )
    (net (code "58") (name "Net-(D238-A)") (class "Default")
      (node (ref "D238") (pin "1") (pinfunction "A_1") (pintype "passive"))
      (node (ref "S238") (pin "1") (pinfunction "1_1") (pintype "passive"))
    )
    (net (code "59") (name "Net-(D239-A)") (class "Default")
      (node (ref "D239") (pin "1") (pinfunction "A_1") (pintype "passive"))
      (node (ref "S239") (pin "1") (pinfunction "1_1") (pintype "passive"))
    )
    (net (code "60") (name "Net-(D240-A)") (class "Default")
      (node (ref "D240") (pin "1") (pinfunction "A_1") (pintype "passive"))
      (node (ref "S240") (pin "1") (pinfunction "1_1") (pintype "passive"))
    )
    (net (code "61") (name "Net-(D241-A)") (class "Default")
      (node (ref "D241") (pin "1") (pinfunction "A_1") (pintype "passive"))
      (node (ref "S241") (pin "1") (pinfunction "1_1") (pintype "passive"))
    )
    (net (code "62") (name "Net-(D242-A)") (class "Default")
      (node (ref "D242") (pin "1") (pinfunction "A_1") (pintype "passive"))
      (node (ref "S242") (pin "1") (pinfunction "1_1") (pintype "passive"))
    )
    (net (code "63") (name "Net-(D243-A)") (class "Default")
      (node (ref "D243") (pin "1") (pinfunction "A_1") (pintype "passive"))
      (node (ref "S243") (pin "1") (pinfunction "1_1") (pintype "passive"))
    )
    (net (code "64") (name "Net-(D244-A)") (class "Default")
      (node (ref "D244") (pin "1") (pinfunction "A_1") (pintype "passive"))
      (node (ref "S244") (pin "1") (pinfunction "1_1") (pintype "passive"))
    )
    (net (code "65") (name "Net-(D245-A)") (class "Default")
      (node (ref "D245") (pin "1") (pinfunction "A_1") (pintype "passive"))
      (node (ref "S245") (pin "1") (pinfunction "1_1") (pintype "passive"))
    )
    (net (code "66") (name "Net-(D246-A)") (class "Default")
      (node (ref "D246") (pin "1") (pinfunction "A_1") (pintype "passive"))
      (node (ref "S246") (pin "1") (pinfunction "1_1") (pintype "passive"))
    )
    (net (code "67") (name "Net-(D247-A)") (class "Default")
      (node (ref "D247") (pin "1") (pinfunction "A_1") (pintype "passive"))
      (node (ref "S247") (pin "1") (pinfunction "1_1") (pintype "passive"))
      (node (ref "S247_1") (pin "1") (pinfunction "1_1") (pintype "passive"))
    )
    (net (code "68") (name "Net-(D248-A)") (class "Default")
      (node (ref "D248") (pin "1") (pinfunction "A_1") (pintype "passive"))
      (node (ref "S248") (pin "1") (pinfunction "1_1") (pintype "passive"))
    )
    (net (code "69") (name "Net-(D249-A)") (class "Default")
      (node (ref "D249") (pin "1") (pinfunction "A_1") (pintype "passive"))
      (node (ref "S249") (pin "1") (pinfunction "1_1") (pintype "passive"))
    )
    (net (code "70") (name "Net-(D250-A)") (class "Default")
      (node (ref "D250") (pin "1") (pinfunction "A_1") (pintype "passive"))
      (node (ref "S250") (pin "1") (pinfunction "1_1") (pintype "passive"))
    )
    (net (code "71") (name "Net-(D251-A)") (class "Default")
      (node (ref "D251") (pin "1") (pinfunction "A_1") (pintype "passive"))
      (node (ref "S251") (pin "1") (pinfunction "1_1") (pintype "passive"))
    )
    (net (code "72") (name "Net-(D252-A)") (class "Default")
      (node (ref "D252") (pin "1") (pinfunction "A_1") (pintype "passive"))
      (node (ref "S252") (pin "1") (pinfunction "1_1") (pintype "passive"))
    )
    (net (code "73") (name "Net-(D253-A)") (class "Default")
      (node (ref "D253") (pin "1") (pinfunction "A_1") (pintype "passive"))
      (node (ref "S253") (pin "1") (pinfunction "1_1") (pintype "passive"))
    )
    (net (code "74") (name "Net-(D254-A)") (class "Default")
      (node (ref "D254") (pin "1") (pinfunction "A_1") (pintype "passive"))
      (node (ref "S254") (pin "1") (pinfunction "1_1") (pintype "passive"))
    )
    (net (code "75") (name "Net-(D255-A)") (class "Default")
      (node (ref "D255") (pin "1") (pinfunction "A_1") (pintype "passive"))
      (node (ref "S255") (pin "1") (pinfunction "1_1") (pintype "passive"))
    )
    (net (code "76") (name "Net-(D256-A)") (class "Default")
      (node (ref "D256") (pin "1") (pinfunction "A_1") (pintype "passive"))
      (node (ref "S256") (pin "1") (pinfunction "1_1") (pintype "passive"))
    )
    (net (code "77") (name "Net-(D257-A)") (class "Default")
      (node (ref "D257") (pin "1") (pinfunction "A_1") (pintype "passive"))
      (node (ref "S257") (pin "1") (pinfunction "1_1") (pintype "passive"))
    )
    (net (code "78") (name "Net-(D258-A)") (class "Default")
      (node (ref "D258") (pin "1") (pinfunction "A_1") (pintype "passive"))
      (node (ref "S258") (pin "1") (pinfunction "1_1") (pintype "passive"))
    )
    (net (code "79") (name "Net-(D259-A)") (class "Default")
      (node (ref "D259") (pin "1") (pinfunction "A_1") (pintype "passive"))
      (node (ref "S259") (pin "1") (pinfunction "1_1") (pintype "passive"))
    )
    (net (code "80") (name "Net-(D260-A)") (class "Default")
      (node (ref "D260") (pin "1") (pinfunction "A_1") (pintype "passive"))
      (node (ref "S260") (pin "1") (pinfunction "1_1") (pintype "passive"))
    )
    (net (code "81") (name "Net-(D261-A)") (class "Default")
      (node (ref "D261") (pin "1") (pinfunction "A_1") (pintype "passive"))
      (node (ref "S261") (pin "1") (pinfunction "1_1") (pintype "passive"))
    )
    (net (code "82") (name "Net-(D262-A)") (class "Default")
      (node (ref "D262") (pin "1") (pinfunction "A_1") (pintype "passive"))
      (node (ref "S262") (pin "1") (pinfunction "1_1") (pintype "passive"))
    )
    (net (code "83") (name "Net-(D263-A)") (class "Default")
      (node (ref "D263") (pin "1") (pinfunction "A_1") (pintype "passive"))
      (node (ref "S263") (pin "1") (pinfunction "1_1") (pintype "passive"))
    )
    (net (code "84") (name "Net-(D264-A)") (class "Default")
      (node (ref "D264") (pin "1") (pinfunction "A_1") (pintype "passive"))
      (node (ref "S264") (pin "1") (pinfunction "1_1") (pintype "passive"))
      (node (ref "S264_1") (pin "1") (pinfunction "1_1") (pintype "passive"))
    )
    (net (code "85") (name "Net-(D265-A)") (class "Default")
      (node (ref "D265") (pin "1") (pinfunction "A_1") (pintype "passive"))
      (node (ref "S265") (pin "1") (pinfunction "1_1") (pintype "passive"))
      (node (ref "S265_1") (pin "1") (pinfunction "1_1") (pintype "passive"))
      (node (ref "S265_2") (pin "1") (pinfunction "1_1") (pintype "passive"))
      (node (ref "S265_3") (pin "1") (pinfunction "1_1") (pintype "passive"))
    )
    (net (code "86") (name "Net-(D266-A)") (class "Default")
      (node (ref "D266") (pin "1") (pinfunction "A_1") (pintype "passive"))
      (node (ref "S266") (pin "1") (pinfunction "1_1") (pintype "passive"))
    )
    (net (code "87") (name "Net-(D267-A)") (class "Default")
      (node (ref "D267") (pin "1") (pinfunction "A_1") (pintype "passive"))
      (node (ref "S267") (pin "1") (pinfunction "1_1") (pintype "passive"))
    )
    (net (code "88") (name "Net-(D268-A)") (class "Default")
      (node (ref "D268") (pin "1") (pinfunction "A_1") (pintype "passive"))
      (node (ref "S268") (pin "1") (pinfunction "1_1") (pintype "passive"))
    )
    (net (code "89") (name "Net-(D269-A)") (class "Default")
      (node (ref "D269") (pin "1") (pinfunction "A_1") (pintype "passive"))
      (node (ref "S269") (pin "1") (pinfunction "1_1") (pintype "passive"))
    )
    (net (code "90") (name "Net-(D270-A)") (class "Default")
      (node (ref "D270") (pin "1") (pinfunction "A_1") (pintype "passive"))
      (node (ref "S270") (pin "1") (pinfunction "1_1") (pintype "passive"))
    )
    (net (code "91") (name "Net-(D271-A)") (class "Default")
      (node (ref "D271") (pin "1") (pinfunction "A_1") (pintype "passive"))
      (node (ref "S271") (pin "1") (pinfunction "1_1") (pintype "passive"))
    )
    (net (code "92") (name "Net-(D272-A)") (class "Default")
      (node (ref "D272") (pin "1") (pinfunction "A_1") (pintype "passive"))
      (node (ref "S272") (pin "1") (pinfunction "1_1") (pintype "passive"))
    )
    (net (code "93") (name "Net-(D273-A)") (class "Default")
      (node (ref "D273") (pin "1") (pinfunction "A_1") (pintype "passive"))
      (node (ref "S273") (pin "1") (pinfunction "1_1") (pintype "passive"))
    )
    (net (code "94") (name "Net-(D274-A)") (class "Default")
      (node (ref "D274") (pin "1") (pinfunction "A_1") (pintype "passive"))
      (node (ref "S274") (pin "1") (pinfunction "1_1") (pintype "passive"))
    )
    (net (code "95") (name "Net-(D275-A)") (class "Default")
      (node (ref "D275") (pin "1") (pinfunction "A_1") (pintype "passive"))
      (node (ref "S275") (pin "1") (pinfunction "1_1") (pintype "passive"))
    )
    (net (code "96") (name "Net-(D276-A)") (class "Default")
      (node (ref "D276") (pin "1") (pinfunction "A_1") (pintype "passive"))
      (node (ref "S276") (pin "1") (pinfunction "1_1") (pintype "passive"))
    )
    (net (code "97") (name "Net-(D277-A)") (class "Default")
      (node (ref "D277") (pin "1") (pinfunction "A_1") (pintype "passive"))
      (node (ref "S277") (pin "1") (pinfunction "1_1") (pintype "passive"))
      (node (ref "S277_1") (pin "1") (pinfunction "1_1") (pintype "passive"))
      (node (ref "S277_2") (pin "1") (pinfunction "1_1") (pintype "passive"))
    )
    (net (code "98") (name "Net-(D278-A)") (class "Default")
      (node (ref "D278") (pin "1") (pinfunction "A_1") (pintype "passive"))
      (node (ref "S278") (pin "1") (pinfunction "1_1") (pintype "passive"))
    )
    (net (code "99") (name "Net-(D279-A)") (class "Default")
      (node (ref "D279") (pin "1") (pinfunction "A_1") (pintype "passive"))
      (node (ref "S279") (pin "1") (pinfunction "1_1") (pintype "passive"))
    )
    (net (code "100") (name "Net-(D280-A)") (class "Default")
      (node (ref "D280") (pin "1") (pinfunction "A_1") (pintype "passive"))
      (node (ref "S280") (pin "2") (pinfunction "2_2") (pintype "passive"))
      (node (ref "S280_1") (pin "1") (pinfunction "1_1") (pintype "passive"))
    )
    (net (code "101") (name "Net-(D281-A)") (class "Default")
      (node (ref "D281") (pin "1") (pinfunction "A_1") (pintype "passive"))
      (node (ref "S281") (pin "2") (pinfunction "2_2") (pintype "passive"))
      (node (ref "S281_1") (pin "1") (pinfunction "1_1") (pintype "passive"))
    )
    (net (code "102") (name "Net-(D282-A)") (class "Default")
      (node (ref "D282") (pin "1") (pinfunction "A_1") (pintype "passive"))
      (node (ref "S282") (pin "2") (pinfunction "2_2") (pintype "passive"))
      (node (ref "S282_1") (pin "1") (pinfunction "1_1") (pintype "passive"))
    )
    (net (code "103") (name "Net-(D283-A)") (class "Default")
      (node (ref "D283") (pin "1") (pinfunction "A_1") (pintype "passive"))
      (node (ref "S283") (pin "1") (pinfunction "1_1") (pintype "passive"))
      (node (ref "S283_1") (pin "1") (pinfunction "1_1") (pintype "passive"))
      (node (ref "S283_2") (pin "1") (pinfunction "1_1") (pintype "passive"))
    )
    (net (code "104") (name "Net-(D284-A)") (class "Default")
      (node (ref "D284") (pin "1") (pinfunction "A_1") (pintype "passive"))
      (node (ref "S284") (pin "1") (pinfunction "1_1") (pintype "passive"))
      (node (ref "S284_1") (pin "1") (pinfunction "1_1") (pintype "passive"))
    )
    (net (code "105") (name "Net-(D285-A)") (class "Default")
      (node (ref "D285") (pin "1") (pinfunction "A_1") (pintype "passive"))
      (node (ref "S285") (pin "1") (pinfunction "1_1") (pintype "passive"))
      (node (ref "S285_1") (pin "1") (pinfunction "1_1") (pintype "passive"))
    )
    (net (code "106") (name "Net-(D286-A)") (class "Default")
      (node (ref "D286") (pin "1") (pinfunction "A_1") (pintype "passive"))
      (node (ref "S286") (pin "1") (pinfunction "1_1") (pintype "passive"))
      (node (ref "S286_1") (pin "1") (pinfunction "1_1") (pintype "passive"))
    )
    (net (code "107") (name "Net-(D287-A)") (class "Default")
      (node (ref "D287") (pin "1") (pinfunction "A_1") (pintype "passive"))
      (node (ref "S287") (pin "1") (pinfunction "1_1") (pintype "passive"))
    )
    (net (code "108") (name "Net-(D288-A)") (class "Default")
      (node (ref "D288") (pin "1") (pinfunction "A_1") (pintype "passive"))
      (node (ref "S288") (pin "1") (pinfunction "1_1") (pintype "passive"))
    )
    (net (code "109") (name "Net-(D289-A)") (class "Default")
      (node (ref "D289") (pin "1") (pinfunction "A_1") (pintype "passive"))
      (node (ref "S289") (pin "1") (pinfunction "1_1") (pintype "passive"))
    )
    (net (code "110") (name "Net-(D290-A)") (class "Default")
      (node (ref "D290") (pin "1") (pinfunction "A_1") (pintype "passive"))
      (node (ref "S290") (pin "1") (pinfunction "1_1") (pintype "passive"))
    )
    (net (code "111") (name "Net-(D293-A)") (class "Default")
      (node (ref "D293") (pin "1") (pinfunction "A_1") (pintype "passive"))
      (node (ref "S293") (pin "1") (pinfunction "1_1") (pintype "passive"))
    )
    (net (code "112") (name "Net-(D294-A)") (class "Default")
      (node (ref "D294") (pin "1") (pinfunction "A_1") (pintype "passive"))
      (node (ref "S294") (pin "2") (pinfunction "2_2") (pintype "passive"))
      (node (ref "S294_2") (pin "1") (pinfunction "1_1") (pintype "passive"))
    )
    (net (code "113") (name "Net-(D295-A)") (class "Default")
      (node (ref "D295") (pin "1") (pinfunction "A_1") (pintype "passive"))
      (node (ref "S295") (pin "2") (pinfunction "2_2") (pintype "passive"))
      (node (ref "S295_2") (pin "1") (pinfunction "1_1") (pintype "passive"))
    )
    (net (code "114") (name "Net-(D296-A)") (class "Default")
      (node (ref "D296") (pin "1") (pinfunction "A_1") (pintype "passive"))
      (node (ref "S296") (pin "1") (pinfunction "1_1") (pintype "passive"))
      (node (ref "S296_1") (pin "1") (pinfunction "1_1") (pintype "passive"))
      (node (ref "S296_2") (pin "1") (pinfunction "1_1") (pintype "passive"))
    )
  )
)
